# led-controller-hw.net
KiCad netlist of a schematic drawn in EAGLE
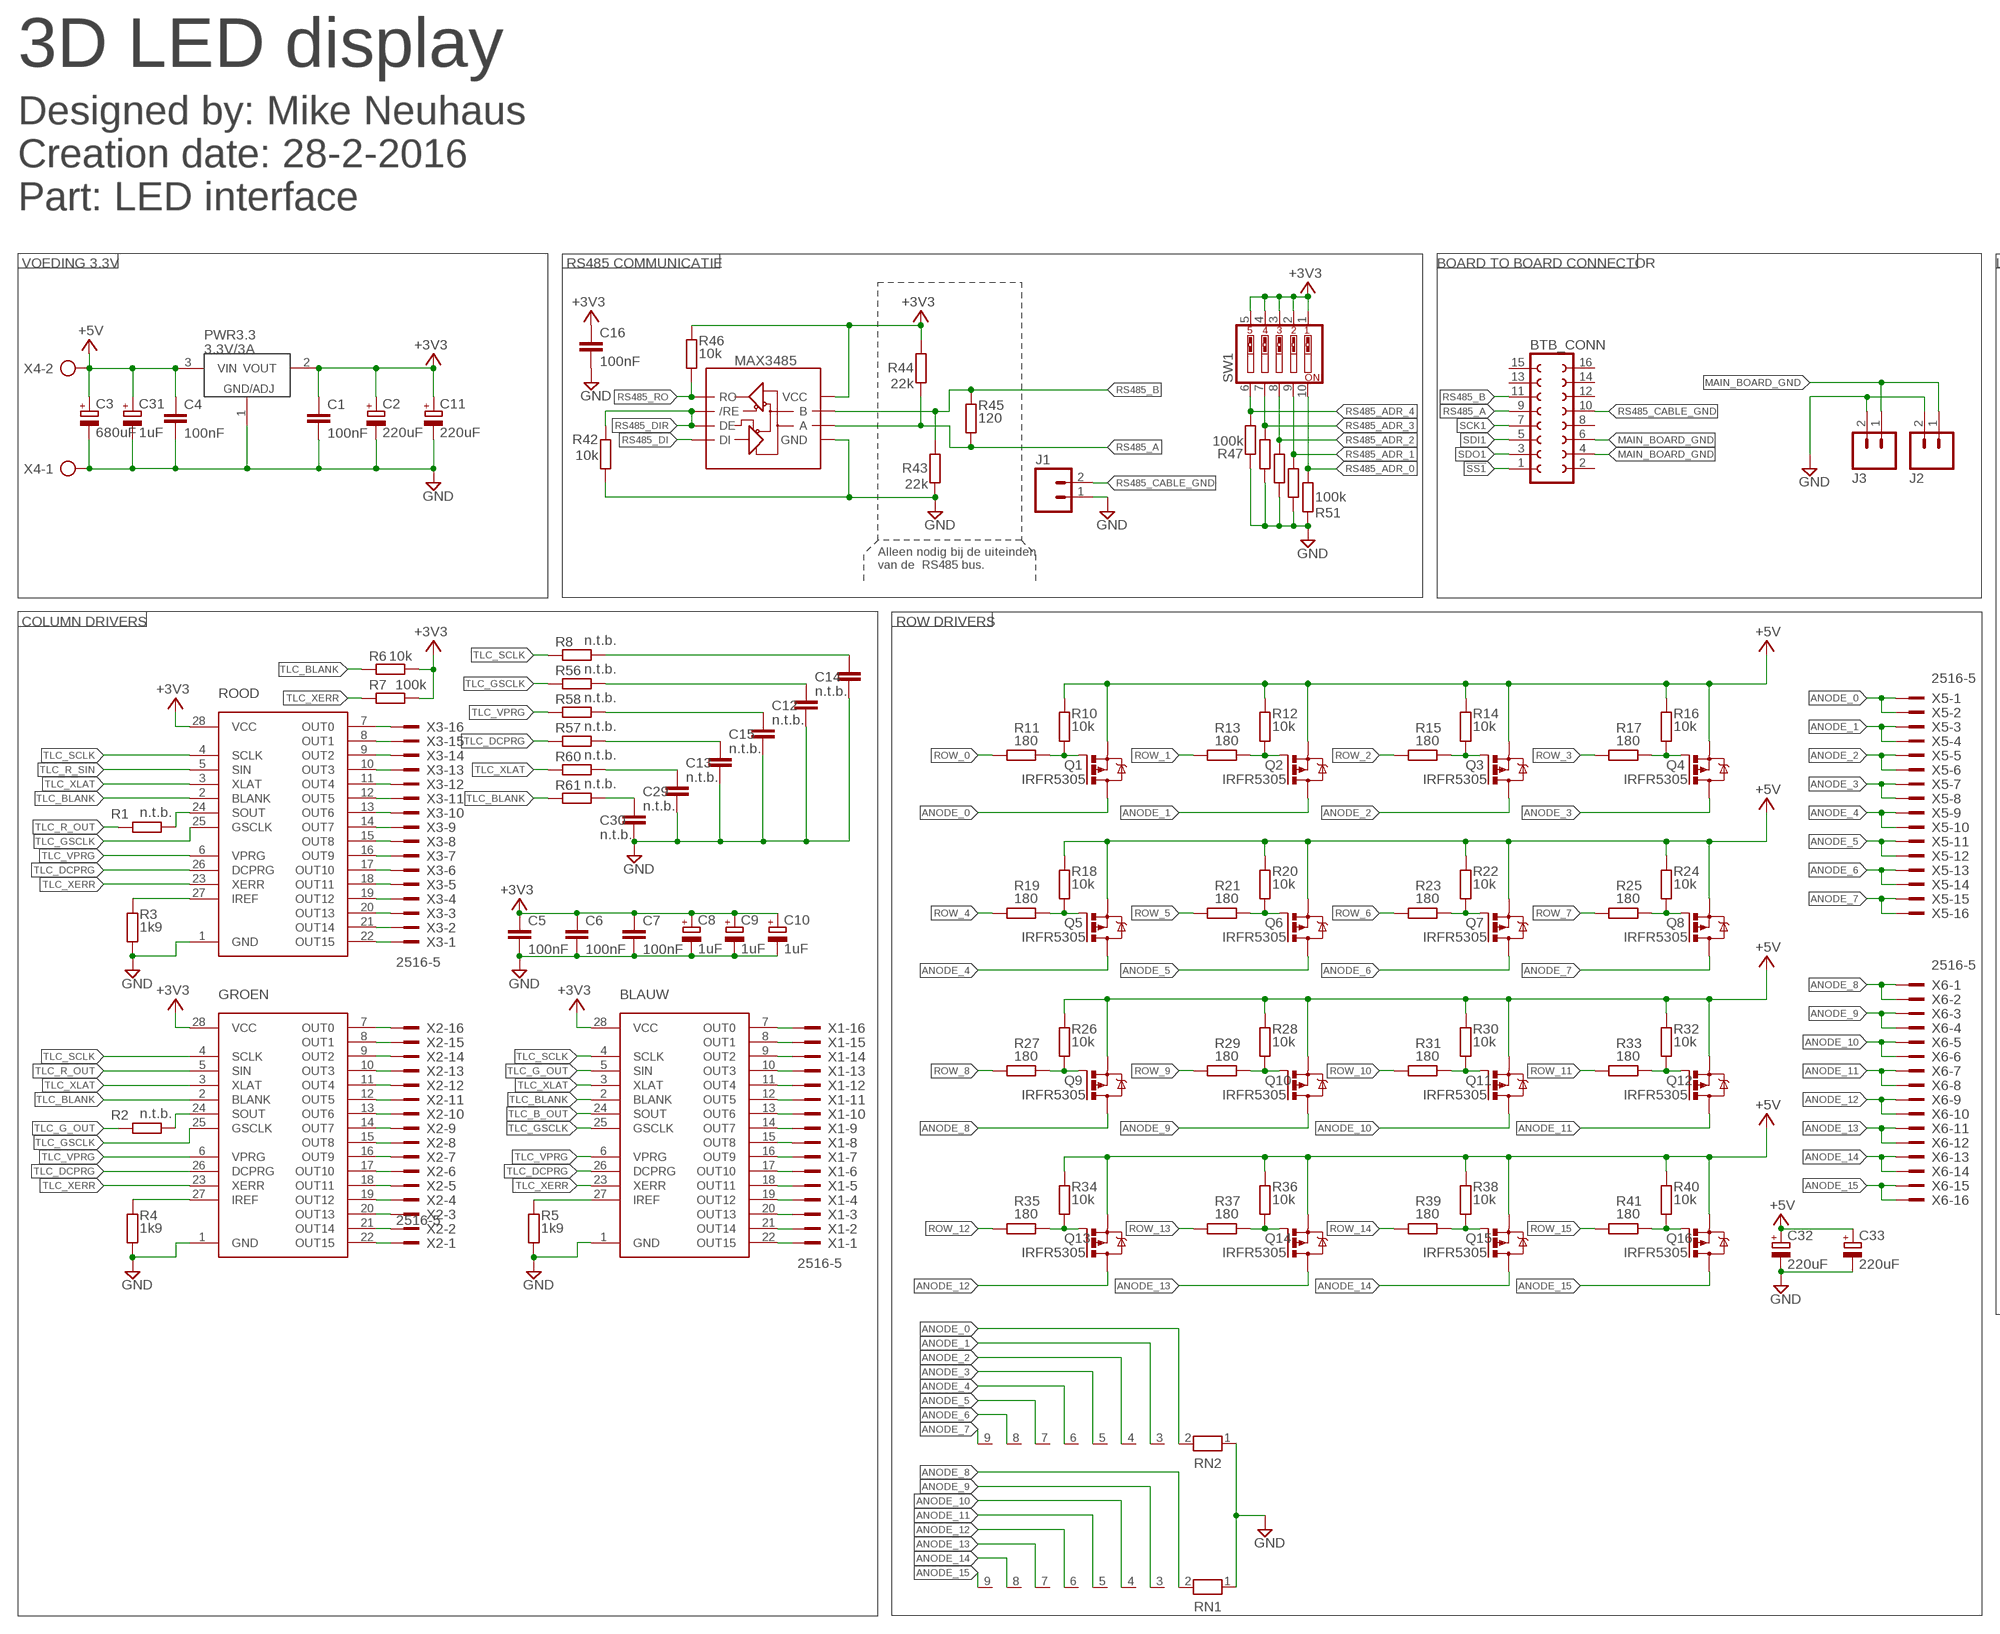
[diagram p0: schematic, sheet 1, part 1 of 2]
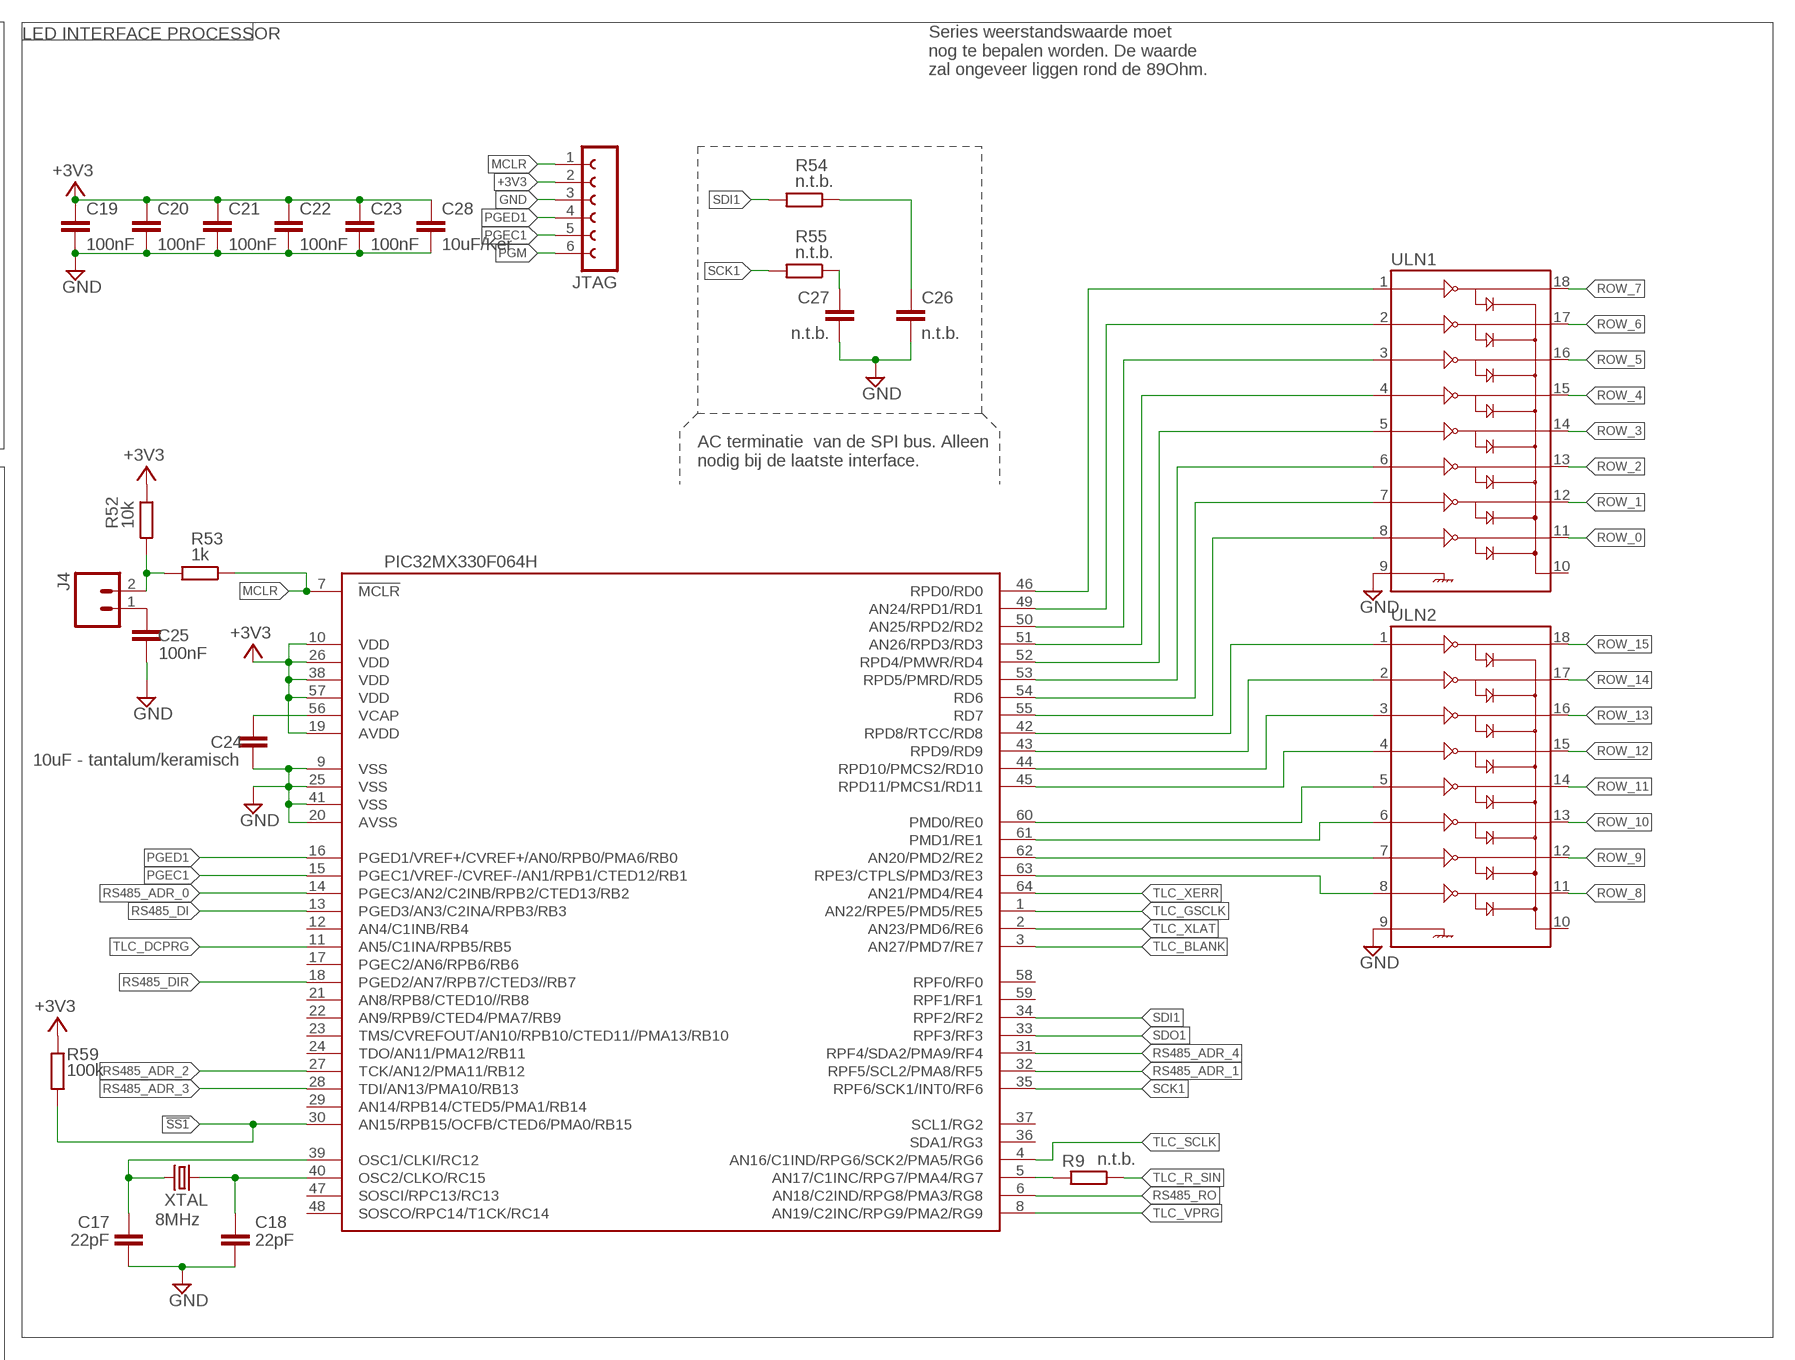
[diagram p1: schematic, sheet 1, part 2 of 2]

(export (version "E")
  (design (tool "Eeschema 10.0.6"))
  (components
    (comp (ref "BLAUW")
      (value "TLC5940PWPR")
      (footprint "eagle-import:TSSOP-28-PWP")
      (libsource (lib "eagle-import") (part "TLC5940PWPR"))
    )
    (comp (ref "BTB_CONN")
      (value "FE08-2W")
      (footprint "eagle-import:FE08-2W")
      (libsource (lib "eagle-import") (part "FE08-2W"))
    )
    (comp (ref "C1")
      (value "100nF")
      (footprint "eagle-import:C0805")
      (libsource (lib "eagle-import") (part "C-EUC0805"))
    )
    (comp (ref "C2")
      (value "220uF")
      (footprint "eagle-import:E2,5-6E")
      (libsource (lib "eagle-import") (part "CPOL-EUE2,5-6E"))
    )
    (comp (ref "C3")
      (value "680uF")
      (footprint "eagle-import:CPOL_EU10-27")
      (libsource (lib "eagle-import") (part "CPOL_EU10-27-5"))
    )
    (comp (ref "C4")
      (value "100nF")
      (footprint "eagle-import:C0805")
      (libsource (lib "eagle-import") (part "C-EUC0805"))
    )
    (comp (ref "C5")
      (value "100nF")
      (footprint "eagle-import:C0805")
      (libsource (lib "eagle-import") (part "C-EUC0805"))
    )
    (comp (ref "C6")
      (value "100nF")
      (footprint "eagle-import:C0805")
      (libsource (lib "eagle-import") (part "C-EUC0805"))
    )
    (comp (ref "C7")
      (value "100nF")
      (footprint "eagle-import:C0805")
      (libsource (lib "eagle-import") (part "C-EUC0805"))
    )
    (comp (ref "C8")
      (value "1uF")
      (footprint "eagle-import:E2,5-5")
      (libsource (lib "eagle-import") (part "CPOL-EUE2.5-5"))
    )
    (comp (ref "C9")
      (value "1uF")
      (footprint "eagle-import:E2,5-5")
      (libsource (lib "eagle-import") (part "CPOL-EUE2.5-5"))
    )
    (comp (ref "C10")
      (value "1uF")
      (footprint "eagle-import:E2,5-5")
      (libsource (lib "eagle-import") (part "CPOL-EUE2.5-5"))
    )
    (comp (ref "C11")
      (value "220uF")
      (footprint "eagle-import:E2,5-6E")
      (libsource (lib "eagle-import") (part "CPOL-EUE2,5-6E"))
    )
    (comp (ref "C12")
      (value "n.t.b.")
      (footprint "eagle-import:C0805")
      (libsource (lib "eagle-import") (part "C-EUC0805"))
    )
    (comp (ref "C13")
      (value "n.t.b.")
      (footprint "eagle-import:C0805")
      (libsource (lib "eagle-import") (part "C-EUC0805"))
    )
    (comp (ref "C14")
      (value "n.t.b.")
      (footprint "eagle-import:C0805")
      (libsource (lib "eagle-import") (part "C-EUC0805"))
    )
    (comp (ref "C15")
      (value "n.t.b.")
      (footprint "eagle-import:C0805")
      (libsource (lib "eagle-import") (part "C-EUC0805"))
    )
    (comp (ref "C16")
      (value "100nF")
      (footprint "eagle-import:C0805")
      (libsource (lib "eagle-import") (part "C-EUC0805"))
    )
    (comp (ref "C17")
      (value "22pF")
      (footprint "eagle-import:C0805")
      (libsource (lib "eagle-import") (part "C-EUC0805"))
    )
    (comp (ref "C18")
      (value "22pF")
      (footprint "eagle-import:C0805")
      (libsource (lib "eagle-import") (part "C-EUC0805"))
    )
    (comp (ref "C19")
      (value "100nF")
      (footprint "eagle-import:C0805")
      (libsource (lib "eagle-import") (part "C-EUC0805"))
    )
    (comp (ref "C20")
      (value "100nF")
      (footprint "eagle-import:C0805")
      (libsource (lib "eagle-import") (part "C-EUC0805"))
    )
    (comp (ref "C21")
      (value "100nF")
      (footprint "eagle-import:C0805")
      (libsource (lib "eagle-import") (part "C-EUC0805"))
    )
    (comp (ref "C22")
      (value "100nF")
      (footprint "eagle-import:C0805")
      (libsource (lib "eagle-import") (part "C-EUC0805"))
    )
    (comp (ref "C23")
      (value "100nF")
      (footprint "eagle-import:C0805")
      (libsource (lib "eagle-import") (part "C-EUC0805"))
    )
    (comp (ref "C24")
      (value "10uF - tantalum/keramisch")
      (footprint "eagle-import:C0805")
      (libsource (lib "eagle-import") (part "C-EUC0805"))
    )
    (comp (ref "C25")
      (value "100nF")
      (footprint "eagle-import:C0805")
      (libsource (lib "eagle-import") (part "C-EUC0805"))
    )
    (comp (ref "C26")
      (value "n.t.b.")
      (footprint "eagle-import:C0805")
      (libsource (lib "eagle-import") (part "C-EUC0805"))
    )
    (comp (ref "C27")
      (value "n.t.b.")
      (footprint "eagle-import:C0805")
      (libsource (lib "eagle-import") (part "C-EUC0805"))
    )
    (comp (ref "C28")
      (value "10uF/Ker")
      (footprint "eagle-import:C0805")
      (libsource (lib "eagle-import") (part "C-EUC0805"))
    )
    (comp (ref "C29")
      (value "n.t.b.")
      (footprint "eagle-import:C0805")
      (libsource (lib "eagle-import") (part "C-EUC0805"))
    )
    (comp (ref "C30")
      (value "n.t.b.")
      (footprint "eagle-import:C0805")
      (libsource (lib "eagle-import") (part "C-EUC0805"))
    )
    (comp (ref "C31")
      (value "1uF")
      (footprint "eagle-import:E2,5-5")
      (libsource (lib "eagle-import") (part "CPOL-EUE2.5-5"))
    )
    (comp (ref "C32")
      (value "220uF")
      (footprint "eagle-import:E2,5-6E")
      (libsource (lib "eagle-import") (part "CPOL-EUE2,5-6E"))
    )
    (comp (ref "C33")
      (value "220uF")
      (footprint "eagle-import:E2,5-6E")
      (libsource (lib "eagle-import") (part "CPOL-EUE2,5-6E"))
    )
    (comp (ref "GROEN")
      (value "TLC5940PWPR")
      (footprint "eagle-import:TSSOP-28-PWP")
      (libsource (lib "eagle-import") (part "TLC5940PWPR"))
    )
    (comp (ref "J1")
      (value "M02LOCK")
      (footprint "eagle-import:1X02_LOCK")
      (libsource (lib "eagle-import") (part "M02LOCK"))
    )
    (comp (ref "J2")
      (value "M02LOCK")
      (footprint "eagle-import:1X02_LOCK")
      (libsource (lib "eagle-import") (part "M02LOCK"))
    )
    (comp (ref "J3")
      (value "M02LOCK")
      (footprint "eagle-import:1X02_LOCK")
      (libsource (lib "eagle-import") (part "M02LOCK"))
    )
    (comp (ref "J4")
      (value "M02LOCK")
      (footprint "eagle-import:1X02_LOCK")
      (libsource (lib "eagle-import") (part "M02LOCK"))
    )
    (comp (ref "JTAG")
      (value "FE06-1")
      (footprint "eagle-import:FE06")
      (libsource (lib "eagle-import") (part "FE06-1"))
    )
    (comp (ref "MAX3485")
      (value "RS485SOIC")
      (footprint "eagle-import:SO08")
      (libsource (lib "eagle-import") (part "RS485SOIC"))
    )
    (comp (ref "PIC32MX330F064H")
      (value "PIC32MX330F064H")
      (footprint "eagle-import:TQFP-64-10")
      (libsource (lib "eagle-import") (part "PIC32MX330F064H"))
    )
    (comp (ref "PWR3.3")
      (value "3.3V/3A")
      (footprint "eagle-import:TO-220")
      (libsource (lib "eagle-import") (part "LM1085-3.3"))
    )
    (comp (ref "Q1")
      (value "IRFR5305")
      (footprint "eagle-import:D-PAK_TO252AA")
      (libsource (lib "eagle-import") (part "IRF?5305R"))
    )
    (comp (ref "Q2")
      (value "IRFR5305")
      (footprint "eagle-import:D-PAK_TO252AA")
      (libsource (lib "eagle-import") (part "IRF?5305R"))
    )
    (comp (ref "Q3")
      (value "IRFR5305")
      (footprint "eagle-import:D-PAK_TO252AA")
      (libsource (lib "eagle-import") (part "IRF?5305R"))
    )
    (comp (ref "Q4")
      (value "IRFR5305")
      (footprint "eagle-import:D-PAK_TO252AA")
      (libsource (lib "eagle-import") (part "IRF?5305R"))
    )
    (comp (ref "Q5")
      (value "IRFR5305")
      (footprint "eagle-import:D-PAK_TO252AA")
      (libsource (lib "eagle-import") (part "IRF?5305R"))
    )
    (comp (ref "Q6")
      (value "IRFR5305")
      (footprint "eagle-import:D-PAK_TO252AA")
      (libsource (lib "eagle-import") (part "IRF?5305R"))
    )
    (comp (ref "Q7")
      (value "IRFR5305")
      (footprint "eagle-import:D-PAK_TO252AA")
      (libsource (lib "eagle-import") (part "IRF?5305R"))
    )
    (comp (ref "Q8")
      (value "IRFR5305")
      (footprint "eagle-import:D-PAK_TO252AA")
      (libsource (lib "eagle-import") (part "IRF?5305R"))
    )
    (comp (ref "Q9")
      (value "IRFR5305")
      (footprint "eagle-import:D-PAK_TO252AA")
      (libsource (lib "eagle-import") (part "IRF?5305R"))
    )
    (comp (ref "Q10")
      (value "IRFR5305")
      (footprint "eagle-import:D-PAK_TO252AA")
      (libsource (lib "eagle-import") (part "IRF?5305R"))
    )
    (comp (ref "Q11")
      (value "IRFR5305")
      (footprint "eagle-import:D-PAK_TO252AA")
      (libsource (lib "eagle-import") (part "IRF?5305R"))
    )
    (comp (ref "Q12")
      (value "IRFR5305")
      (footprint "eagle-import:D-PAK_TO252AA")
      (libsource (lib "eagle-import") (part "IRF?5305R"))
    )
    (comp (ref "Q13")
      (value "IRFR5305")
      (footprint "eagle-import:D-PAK_TO252AA")
      (libsource (lib "eagle-import") (part "IRF?5305R"))
    )
    (comp (ref "Q14")
      (value "IRFR5305")
      (footprint "eagle-import:D-PAK_TO252AA")
      (libsource (lib "eagle-import") (part "IRF?5305R"))
    )
    (comp (ref "Q15")
      (value "IRFR5305")
      (footprint "eagle-import:D-PAK_TO252AA")
      (libsource (lib "eagle-import") (part "IRF?5305R"))
    )
    (comp (ref "Q16")
      (value "IRFR5305")
      (footprint "eagle-import:D-PAK_TO252AA")
      (libsource (lib "eagle-import") (part "IRF?5305R"))
    )
    (comp (ref "R1")
      (value "n.t.b.")
      (footprint "eagle-import:M0805")
      (libsource (lib "eagle-import") (part "R-EU_M0805"))
    )
    (comp (ref "R2")
      (value "n.t.b.")
      (footprint "eagle-import:M0805")
      (libsource (lib "eagle-import") (part "R-EU_M0805"))
    )
    (comp (ref "R3")
      (value "1k9")
      (footprint "eagle-import:M0805")
      (libsource (lib "eagle-import") (part "R-EU_M0805"))
    )
    (comp (ref "R4")
      (value "1k9")
      (footprint "eagle-import:M0805")
      (libsource (lib "eagle-import") (part "R-EU_M0805"))
    )
    (comp (ref "R5")
      (value "1k9")
      (footprint "eagle-import:M0805")
      (libsource (lib "eagle-import") (part "R-EU_M0805"))
    )
    (comp (ref "R6")
      (value "10k")
      (footprint "eagle-import:M0805")
      (libsource (lib "eagle-import") (part "R-EU_M0805"))
    )
    (comp (ref "R7")
      (value "100k")
      (footprint "eagle-import:M0805")
      (libsource (lib "eagle-import") (part "R-EU_M0805"))
    )
    (comp (ref "R8")
      (value "n.t.b.")
      (footprint "eagle-import:M0805")
      (libsource (lib "eagle-import") (part "R-EU_M0805"))
    )
    (comp (ref "R9")
      (value "n.t.b.")
      (footprint "eagle-import:M0805")
      (libsource (lib "eagle-import") (part "R-EU_M0805"))
    )
    (comp (ref "R10")
      (value "10k")
      (footprint "eagle-import:M0805")
      (libsource (lib "eagle-import") (part "R-EU_M0805"))
    )
    (comp (ref "R11")
      (value "180")
      (footprint "eagle-import:M0805")
      (libsource (lib "eagle-import") (part "R-EU_M0805"))
    )
    (comp (ref "R12")
      (value "10k")
      (footprint "eagle-import:M0805")
      (libsource (lib "eagle-import") (part "R-EU_M0805"))
    )
    (comp (ref "R13")
      (value "180")
      (footprint "eagle-import:M0805")
      (libsource (lib "eagle-import") (part "R-EU_M0805"))
    )
    (comp (ref "R14")
      (value "10k")
      (footprint "eagle-import:M0805")
      (libsource (lib "eagle-import") (part "R-EU_M0805"))
    )
    (comp (ref "R15")
      (value "180")
      (footprint "eagle-import:M0805")
      (libsource (lib "eagle-import") (part "R-EU_M0805"))
    )
    (comp (ref "R16")
      (value "10k")
      (footprint "eagle-import:M0805")
      (libsource (lib "eagle-import") (part "R-EU_M0805"))
    )
    (comp (ref "R17")
      (value "180")
      (footprint "eagle-import:M0805")
      (libsource (lib "eagle-import") (part "R-EU_M0805"))
    )
    (comp (ref "R18")
      (value "10k")
      (footprint "eagle-import:M0805")
      (libsource (lib "eagle-import") (part "R-EU_M0805"))
    )
    (comp (ref "R19")
      (value "180")
      (footprint "eagle-import:M0805")
      (libsource (lib "eagle-import") (part "R-EU_M0805"))
    )
    (comp (ref "R20")
      (value "10k")
      (footprint "eagle-import:M0805")
      (libsource (lib "eagle-import") (part "R-EU_M0805"))
    )
    (comp (ref "R21")
      (value "180")
      (footprint "eagle-import:M0805")
      (libsource (lib "eagle-import") (part "R-EU_M0805"))
    )
    (comp (ref "R22")
      (value "10k")
      (footprint "eagle-import:M0805")
      (libsource (lib "eagle-import") (part "R-EU_M0805"))
    )
    (comp (ref "R23")
      (value "180")
      (footprint "eagle-import:M0805")
      (libsource (lib "eagle-import") (part "R-EU_M0805"))
    )
    (comp (ref "R24")
      (value "10k")
      (footprint "eagle-import:M0805")
      (libsource (lib "eagle-import") (part "R-EU_M0805"))
    )
    (comp (ref "R25")
      (value "180")
      (footprint "eagle-import:M0805")
      (libsource (lib "eagle-import") (part "R-EU_M0805"))
    )
    (comp (ref "R26")
      (value "10k")
      (footprint "eagle-import:M0805")
      (libsource (lib "eagle-import") (part "R-EU_M0805"))
    )
    (comp (ref "R27")
      (value "180")
      (footprint "eagle-import:M0805")
      (libsource (lib "eagle-import") (part "R-EU_M0805"))
    )
    (comp (ref "R28")
      (value "10k")
      (footprint "eagle-import:M0805")
      (libsource (lib "eagle-import") (part "R-EU_M0805"))
    )
    (comp (ref "R29")
      (value "180")
      (footprint "eagle-import:M0805")
      (libsource (lib "eagle-import") (part "R-EU_M0805"))
    )
    (comp (ref "R30")
      (value "10k")
      (footprint "eagle-import:M0805")
      (libsource (lib "eagle-import") (part "R-EU_M0805"))
    )
    (comp (ref "R31")
      (value "180")
      (footprint "eagle-import:M0805")
      (libsource (lib "eagle-import") (part "R-EU_M0805"))
    )
    (comp (ref "R32")
      (value "10k")
      (footprint "eagle-import:M0805")
      (libsource (lib "eagle-import") (part "R-EU_M0805"))
    )
    (comp (ref "R33")
      (value "180")
      (footprint "eagle-import:M0805")
      (libsource (lib "eagle-import") (part "R-EU_M0805"))
    )
    (comp (ref "R34")
      (value "10k")
      (footprint "eagle-import:M0805")
      (libsource (lib "eagle-import") (part "R-EU_M0805"))
    )
    (comp (ref "R35")
      (value "180")
      (footprint "eagle-import:M0805")
      (libsource (lib "eagle-import") (part "R-EU_M0805"))
    )
    (comp (ref "R36")
      (value "10k")
      (footprint "eagle-import:M0805")
      (libsource (lib "eagle-import") (part "R-EU_M0805"))
    )
    (comp (ref "R37")
      (value "180")
      (footprint "eagle-import:M0805")
      (libsource (lib "eagle-import") (part "R-EU_M0805"))
    )
    (comp (ref "R38")
      (value "10k")
      (footprint "eagle-import:M0805")
      (libsource (lib "eagle-import") (part "R-EU_M0805"))
    )
    (comp (ref "R39")
      (value "180")
      (footprint "eagle-import:M0805")
      (libsource (lib "eagle-import") (part "R-EU_M0805"))
    )
    (comp (ref "R40")
      (value "10k")
      (footprint "eagle-import:M0805")
      (libsource (lib "eagle-import") (part "R-EU_M0805"))
    )
    (comp (ref "R41")
      (value "180")
      (footprint "eagle-import:M0805")
      (libsource (lib "eagle-import") (part "R-EU_M0805"))
    )
    (comp (ref "R42")
      (value "10k")
      (footprint "eagle-import:M0805")
      (libsource (lib "eagle-import") (part "R-EU_M0805"))
    )
    (comp (ref "R43")
      (value "22k")
      (footprint "eagle-import:M0805")
      (libsource (lib "eagle-import") (part "R-EU_M0805"))
    )
    (comp (ref "R44")
      (value "22k")
      (footprint "eagle-import:M0805")
      (libsource (lib "eagle-import") (part "R-EU_M0805"))
    )
    (comp (ref "R45")
      (value "120")
      (footprint "eagle-import:M0805")
      (libsource (lib "eagle-import") (part "R-EU_M0805"))
    )
    (comp (ref "R46")
      (value "10k")
      (footprint "eagle-import:M0805")
      (libsource (lib "eagle-import") (part "R-EU_M0805"))
    )
    (comp (ref "R47")
      (value "100k")
      (footprint "eagle-import:M0805")
      (libsource (lib "eagle-import") (part "R-EU_M0805"))
    )
    (comp (ref "R48")
      (value "100k")
      (footprint "eagle-import:M0805")
      (libsource (lib "eagle-import") (part "R-EU_M0805"))
    )
    (comp (ref "R49")
      (value "100k")
      (footprint "eagle-import:M0805")
      (libsource (lib "eagle-import") (part "R-EU_M0805"))
    )
    (comp (ref "R50")
      (value "100k")
      (footprint "eagle-import:M0805")
      (libsource (lib "eagle-import") (part "R-EU_M0805"))
    )
    (comp (ref "R51")
      (value "100k")
      (footprint "eagle-import:M0805")
      (libsource (lib "eagle-import") (part "R-EU_M0805"))
    )
    (comp (ref "R52")
      (value "10k")
      (footprint "eagle-import:M0805")
      (libsource (lib "eagle-import") (part "R-EU_M0805"))
    )
    (comp (ref "R53")
      (value "1k")
      (footprint "eagle-import:M0805")
      (libsource (lib "eagle-import") (part "R-EU_M0805"))
    )
    (comp (ref "R54")
      (value "n.t.b.")
      (footprint "eagle-import:M0805")
      (libsource (lib "eagle-import") (part "R-EU_M0805"))
    )
    (comp (ref "R55")
      (value "n.t.b.")
      (footprint "eagle-import:M0805")
      (libsource (lib "eagle-import") (part "R-EU_M0805"))
    )
    (comp (ref "R56")
      (value "n.t.b.")
      (footprint "eagle-import:M0805")
      (libsource (lib "eagle-import") (part "R-EU_M0805"))
    )
    (comp (ref "R57")
      (value "n.t.b.")
      (footprint "eagle-import:M0805")
      (libsource (lib "eagle-import") (part "R-EU_M0805"))
    )
    (comp (ref "R58")
      (value "n.t.b.")
      (footprint "eagle-import:M0805")
      (libsource (lib "eagle-import") (part "R-EU_M0805"))
    )
    (comp (ref "R59")
      (value "100k")
      (footprint "eagle-import:M0805")
      (libsource (lib "eagle-import") (part "R-EU_M0805"))
    )
    (comp (ref "R60")
      (value "n.t.b.")
      (footprint "eagle-import:M0805")
      (libsource (lib "eagle-import") (part "R-EU_M0805"))
    )
    (comp (ref "R61")
      (value "n.t.b.")
      (footprint "eagle-import:M0805")
      (libsource (lib "eagle-import") (part "R-EU_M0805"))
    )
    (comp (ref "RN1")
      (value "RN08")
      (footprint "eagle-import:RN-9")
      (libsource (lib "eagle-import") (part "RN08"))
    )
    (comp (ref "RN2")
      (value "RN08")
      (footprint "eagle-import:RN-9")
      (libsource (lib "eagle-import") (part "RN08"))
    )
    (comp (ref "ROOD")
      (value "TLC5940PWPR")
      (footprint "eagle-import:TSSOP-28-PWP")
      (libsource (lib "eagle-import") (part "TLC5940PWPR"))
    )
    (comp (ref "SW1")
      (value "SW_DIP-5")
      (footprint "eagle-import:EDG-05")
      (libsource (lib "eagle-import") (part "SW_DIP-5"))
    )
    (comp (ref "ULN1")
      (value "ULN2803SOICW")
      (footprint "eagle-import:SO18L")
      (libsource (lib "eagle-import") (part "ULN2803SOICW"))
    )
    (comp (ref "ULN2")
      (value "ULN2803SOICW")
      (footprint "eagle-import:SO18L")
      (libsource (lib "eagle-import") (part "ULN2803SOICW"))
    )
    (comp (ref "X1")
      (value "2516-5")
      (footprint "eagle-import:PAK100_2500-5-16")
      (fields (field (name "MPN") "D2516-5002-AR"))
      (libsource (lib "eagle-import") (part "2516-5"))
    )
    (comp (ref "X2")
      (value "2516-5")
      (footprint "eagle-import:PAK100_2500-5-16")
      (fields (field (name "MPN") "D2516-5002-AR"))
      (libsource (lib "eagle-import") (part "2516-5"))
    )
    (comp (ref "X3")
      (value "2516-5")
      (footprint "eagle-import:PAK100_2500-5-16")
      (fields (field (name "MPN") "D2516-5002-AR"))
      (libsource (lib "eagle-import") (part "2516-5"))
    )
    (comp (ref "X4")
      (value "AK500/2-H")
      (footprint "eagle-import:AK500_2-H")
      (libsource (lib "eagle-import") (part "AK500/2-H"))
    )
    (comp (ref "X5")
      (value "2516-5")
      (footprint "eagle-import:PAK100_2500-5-16")
      (fields (field (name "MPN") "D2516-5002-AR"))
      (libsource (lib "eagle-import") (part "2516-5"))
    )
    (comp (ref "X6")
      (value "2516-5")
      (footprint "eagle-import:PAK100_2500-5-16")
      (fields (field (name "MPN") "D2516-5002-AR"))
      (libsource (lib "eagle-import") (part "2516-5"))
    )
    (comp (ref "XTAL")
      (value "8MHz")
      (footprint "eagle-import:CSM-7X-DU")
      (libsource (lib "eagle-import") (part "CSM-7X-DU"))
    )
  )
  (nets
    (net (code "1") (name "+3V3") (class "Default")
      (node (ref "BLAUW") (pin "28") (pinfunction "VCC_28") (pintype "power_in"))
      (node (ref "C1") (pin "1") (pinfunction "1_1") (pintype "passive"))
      (node (ref "C10") (pin "+") (pinfunction "+_+") (pintype "passive"))
      (node (ref "C11") (pin "+") (pinfunction "+_+") (pintype "passive"))
      (node (ref "C16") (pin "1") (pinfunction "1_1") (pintype "passive"))
      (node (ref "C19") (pin "1") (pinfunction "1_1") (pintype "passive"))
      (node (ref "C2") (pin "+") (pinfunction "+_+") (pintype "passive"))
      (node (ref "C20") (pin "1") (pinfunction "1_1") (pintype "passive"))
      (node (ref "C21") (pin "1") (pinfunction "1_1") (pintype "passive"))
      (node (ref "C22") (pin "1") (pinfunction "1_1") (pintype "passive"))
      (node (ref "C23") (pin "1") (pinfunction "1_1") (pintype "passive"))
      (node (ref "C28") (pin "1") (pinfunction "1_1") (pintype "passive"))
      (node (ref "C5") (pin "1") (pinfunction "1_1") (pintype "passive"))
      (node (ref "C6") (pin "1") (pinfunction "1_1") (pintype "passive"))
      (node (ref "C7") (pin "1") (pinfunction "1_1") (pintype "passive"))
      (node (ref "C8") (pin "+") (pinfunction "+_+") (pintype "passive"))
      (node (ref "C9") (pin "+") (pinfunction "+_+") (pintype "passive"))
      (node (ref "GROEN") (pin "28") (pinfunction "VCC_28") (pintype "power_in"))
      (node (ref "JTAG") (pin "2") (pinfunction "2_2") (pintype "passive"))
      (node (ref "MAX3485") (pin "8") (pinfunction "VCC_8") (pintype "bidirectional"))
      (node (ref "PIC32MX330F064H") (pin "10") (pinfunction "VDD_10") (pintype "power_in"))
      (node (ref "PIC32MX330F064H") (pin "19") (pinfunction "AVDD_19") (pintype "power_in"))
      (node (ref "PIC32MX330F064H") (pin "26") (pinfunction "VDD_26") (pintype "power_in"))
      (node (ref "PIC32MX330F064H") (pin "38") (pinfunction "VDD_38") (pintype "power_in"))
      (node (ref "PIC32MX330F064H") (pin "57") (pinfunction "VDD_57") (pintype "power_in"))
      (node (ref "PWR3.3") (pin "2") (pinfunction "VOUT_2") (pintype "power_in"))
      (node (ref "R44") (pin "1") (pinfunction "1_1") (pintype "passive"))
      (node (ref "R46") (pin "2") (pinfunction "2_2") (pintype "passive"))
      (node (ref "R52") (pin "1") (pinfunction "1_1") (pintype "passive"))
      (node (ref "R59") (pin "1") (pinfunction "1_1") (pintype "passive"))
      (node (ref "R6") (pin "2") (pinfunction "2_2") (pintype "passive"))
      (node (ref "R7") (pin "2") (pinfunction "2_2") (pintype "passive"))
      (node (ref "ROOD") (pin "28") (pinfunction "VCC_28") (pintype "power_in"))
      (node (ref "SW1") (pin "1") (pinfunction "1_1") (pintype "passive"))
      (node (ref "SW1") (pin "2") (pinfunction "2_2") (pintype "passive"))
      (node (ref "SW1") (pin "3") (pinfunction "3_3") (pintype "passive"))
      (node (ref "SW1") (pin "4") (pinfunction "4_4") (pintype "passive"))
      (node (ref "SW1") (pin "5") (pinfunction "5_5") (pintype "passive"))
    )
    (net (code "2") (name "+5V") (class "Default")
      (node (ref "C3") (pin "1") (pinfunction "+_1") (pintype "passive"))
      (node (ref "C31") (pin "+") (pinfunction "+_+") (pintype "passive"))
      (node (ref "C32") (pin "+") (pinfunction "+_+") (pintype "passive"))
      (node (ref "C33") (pin "+") (pinfunction "+_+") (pintype "passive"))
      (node (ref "C4") (pin "1") (pinfunction "1_1") (pintype "passive"))
      (node (ref "PWR3.3") (pin "3") (pinfunction "VIN_3") (pintype "power_in"))
      (node (ref "Q1") (pin "3") (pinfunction "S_3") (pintype "passive"))
      (node (ref "Q10") (pin "3") (pinfunction "S_3") (pintype "passive"))
      (node (ref "Q11") (pin "3") (pinfunction "S_3") (pintype "passive"))
      (node (ref "Q12") (pin "3") (pinfunction "S_3") (pintype "passive"))
      (node (ref "Q13") (pin "3") (pinfunction "S_3") (pintype "passive"))
      (node (ref "Q14") (pin "3") (pinfunction "S_3") (pintype "passive"))
      (node (ref "Q15") (pin "3") (pinfunction "S_3") (pintype "passive"))
      (node (ref "Q16") (pin "3") (pinfunction "S_3") (pintype "passive"))
      (node (ref "Q2") (pin "3") (pinfunction "S_3") (pintype "passive"))
      (node (ref "Q3") (pin "3") (pinfunction "S_3") (pintype "passive"))
      (node (ref "Q4") (pin "3") (pinfunction "S_3") (pintype "passive"))
      (node (ref "Q5") (pin "3") (pinfunction "S_3") (pintype "passive"))
      (node (ref "Q6") (pin "3") (pinfunction "S_3") (pintype "passive"))
      (node (ref "Q7") (pin "3") (pinfunction "S_3") (pintype "passive"))
      (node (ref "Q8") (pin "3") (pinfunction "S_3") (pintype "passive"))
      (node (ref "Q9") (pin "3") (pinfunction "S_3") (pintype "passive"))
      (node (ref "R10") (pin "2") (pinfunction "2_2") (pintype "passive"))
      (node (ref "R12") (pin "2") (pinfunction "2_2") (pintype "passive"))
      (node (ref "R14") (pin "2") (pinfunction "2_2") (pintype "passive"))
      (node (ref "R16") (pin "2") (pinfunction "2_2") (pintype "passive"))
      (node (ref "R18") (pin "2") (pinfunction "2_2") (pintype "passive"))
      (node (ref "R20") (pin "2") (pinfunction "2_2") (pintype "passive"))
      (node (ref "R22") (pin "2") (pinfunction "2_2") (pintype "passive"))
      (node (ref "R24") (pin "2") (pinfunction "2_2") (pintype "passive"))
      (node (ref "R26") (pin "2") (pinfunction "2_2") (pintype "passive"))
      (node (ref "R28") (pin "2") (pinfunction "2_2") (pintype "passive"))
      (node (ref "R30") (pin "2") (pinfunction "2_2") (pintype "passive"))
      (node (ref "R32") (pin "2") (pinfunction "2_2") (pintype "passive"))
      (node (ref "R34") (pin "2") (pinfunction "2_2") (pintype "passive"))
      (node (ref "R36") (pin "2") (pinfunction "2_2") (pintype "passive"))
      (node (ref "R38") (pin "2") (pinfunction "2_2") (pintype "passive"))
      (node (ref "R40") (pin "2") (pinfunction "2_2") (pintype "passive"))
      (node (ref "X4") (pin "2") (pinfunction "KL_2") (pintype "passive"))
    )
    (net (code "3") (name "/~{SS1}") (class "Default")
      (node (ref "BTB_CONN") (pin "1") (pinfunction "1_1") (pintype "passive"))
      (node (ref "PIC32MX330F064H") (pin "30") (pinfunction "AN15/RPB15/OCFB/CTED6/PMA0/RB15_30") (pintype "bidirectional"))
      (node (ref "R59") (pin "2") (pinfunction "2_2") (pintype "passive"))
    )
    (net (code "4") (name "ANODE_0") (class "Default")
      (node (ref "Q1") (pin "4") (pinfunction "D_4") (pintype "passive"))
      (node (ref "RN2") (pin "2") (pinfunction "2_2") (pintype "passive"))
      (node (ref "X5") (pin "1") (pinfunction "KL_1") (pintype "passive"))
      (node (ref "X5") (pin "2") (pinfunction "KL_2") (pintype "passive"))
    )
    (net (code "5") (name "ANODE_1") (class "Default")
      (node (ref "Q2") (pin "4") (pinfunction "D_4") (pintype "passive"))
      (node (ref "RN2") (pin "3") (pinfunction "3_3") (pintype "passive"))
      (node (ref "X5") (pin "3") (pinfunction "KL_3") (pintype "passive"))
      (node (ref "X5") (pin "4") (pinfunction "KL_4") (pintype "passive"))
    )
    (net (code "6") (name "ANODE_2") (class "Default")
      (node (ref "Q3") (pin "4") (pinfunction "D_4") (pintype "passive"))
      (node (ref "RN2") (pin "4") (pinfunction "4_4") (pintype "passive"))
      (node (ref "X5") (pin "5") (pinfunction "KL_5") (pintype "passive"))
      (node (ref "X5") (pin "6") (pinfunction "KL_6") (pintype "passive"))
    )
    (net (code "7") (name "ANODE_3") (class "Default")
      (node (ref "Q4") (pin "4") (pinfunction "D_4") (pintype "passive"))
      (node (ref "RN2") (pin "5") (pinfunction "5_5") (pintype "passive"))
      (node (ref "X5") (pin "7") (pinfunction "KL_7") (pintype "passive"))
      (node (ref "X5") (pin "8") (pinfunction "KL_8") (pintype "passive"))
    )
    (net (code "8") (name "ANODE_4") (class "Default")
      (node (ref "Q5") (pin "4") (pinfunction "D_4") (pintype "passive"))
      (node (ref "RN2") (pin "6") (pinfunction "6_6") (pintype "passive"))
      (node (ref "X5") (pin "10") (pinfunction "KL_10") (pintype "passive"))
      (node (ref "X5") (pin "9") (pinfunction "KL_9") (pintype "passive"))
    )
    (net (code "9") (name "ANODE_5") (class "Default")
      (node (ref "Q6") (pin "4") (pinfunction "D_4") (pintype "passive"))
      (node (ref "RN2") (pin "7") (pinfunction "7_7") (pintype "passive"))
      (node (ref "X5") (pin "11") (pinfunction "KL_11") (pintype "passive"))
      (node (ref "X5") (pin "12") (pinfunction "KL_12") (pintype "passive"))
    )
    (net (code "10") (name "ANODE_6") (class "Default")
      (node (ref "Q7") (pin "4") (pinfunction "D_4") (pintype "passive"))
      (node (ref "RN2") (pin "8") (pinfunction "8_8") (pintype "passive"))
      (node (ref "X5") (pin "13") (pinfunction "KL_13") (pintype "passive"))
      (node (ref "X5") (pin "14") (pinfunction "KL_14") (pintype "passive"))
    )
    (net (code "11") (name "ANODE_7") (class "Default")
      (node (ref "Q8") (pin "4") (pinfunction "D_4") (pintype "passive"))
      (node (ref "RN2") (pin "9") (pinfunction "9_9") (pintype "passive"))
      (node (ref "X5") (pin "15") (pinfunction "KL_15") (pintype "passive"))
      (node (ref "X5") (pin "16") (pinfunction "KL_16") (pintype "passive"))
    )
    (net (code "12") (name "ANODE_8") (class "Default")
      (node (ref "Q9") (pin "4") (pinfunction "D_4") (pintype "passive"))
      (node (ref "RN1") (pin "2") (pinfunction "2_2") (pintype "passive"))
      (node (ref "X6") (pin "1") (pinfunction "KL_1") (pintype "passive"))
      (node (ref "X6") (pin "2") (pinfunction "KL_2") (pintype "passive"))
    )
    (net (code "13") (name "ANODE_9") (class "Default")
      (node (ref "Q10") (pin "4") (pinfunction "D_4") (pintype "passive"))
      (node (ref "RN1") (pin "3") (pinfunction "3_3") (pintype "passive"))
      (node (ref "X6") (pin "3") (pinfunction "KL_3") (pintype "passive"))
      (node (ref "X6") (pin "4") (pinfunction "KL_4") (pintype "passive"))
    )
    (net (code "14") (name "ANODE_10") (class "Default")
      (node (ref "Q11") (pin "4") (pinfunction "D_4") (pintype "passive"))
      (node (ref "RN1") (pin "4") (pinfunction "4_4") (pintype "passive"))
      (node (ref "X6") (pin "5") (pinfunction "KL_5") (pintype "passive"))
      (node (ref "X6") (pin "6") (pinfunction "KL_6") (pintype "passive"))
    )
    (net (code "15") (name "ANODE_11") (class "Default")
      (node (ref "Q12") (pin "4") (pinfunction "D_4") (pintype "passive"))
      (node (ref "RN1") (pin "5") (pinfunction "5_5") (pintype "passive"))
      (node (ref "X6") (pin "7") (pinfunction "KL_7") (pintype "passive"))
      (node (ref "X6") (pin "8") (pinfunction "KL_8") (pintype "passive"))
    )
    (net (code "16") (name "ANODE_12") (class "Default")
      (node (ref "Q13") (pin "4") (pinfunction "D_4") (pintype "passive"))
      (node (ref "RN1") (pin "6") (pinfunction "6_6") (pintype "passive"))
      (node (ref "X6") (pin "10") (pinfunction "KL_10") (pintype "passive"))
      (node (ref "X6") (pin "9") (pinfunction "KL_9") (pintype "passive"))
    )
    (net (code "17") (name "ANODE_13") (class "Default")
      (node (ref "Q14") (pin "4") (pinfunction "D_4") (pintype "passive"))
      (node (ref "RN1") (pin "7") (pinfunction "7_7") (pintype "passive"))
      (node (ref "X6") (pin "11") (pinfunction "KL_11") (pintype "passive"))
      (node (ref "X6") (pin "12") (pinfunction "KL_12") (pintype "passive"))
    )
    (net (code "18") (name "ANODE_14") (class "Default")
      (node (ref "Q15") (pin "4") (pinfunction "D_4") (pintype "passive"))
      (node (ref "RN1") (pin "8") (pinfunction "8_8") (pintype "passive"))
      (node (ref "X6") (pin "13") (pinfunction "KL_13") (pintype "passive"))
      (node (ref "X6") (pin "14") (pinfunction "KL_14") (pintype "passive"))
    )
    (net (code "19") (name "ANODE_15") (class "Default")
      (node (ref "Q16") (pin "4") (pinfunction "D_4") (pintype "passive"))
      (node (ref "RN1") (pin "9") (pinfunction "9_9") (pintype "passive"))
      (node (ref "X6") (pin "15") (pinfunction "KL_15") (pintype "passive"))
      (node (ref "X6") (pin "16") (pinfunction "KL_16") (pintype "passive"))
    )
    (net (code "20") (name "GND") (class "Default")
      (node (ref "BLAUW") (pin "1") (pinfunction "GND_1") (pintype "power_in"))
      (node (ref "C1") (pin "2") (pinfunction "2_2") (pintype "passive"))
      (node (ref "C10") (pin "-") (pinfunction "-_-") (pintype "passive"))
      (node (ref "C11") (pin "-") (pinfunction "-_-") (pintype "passive"))
      (node (ref "C12") (pin "2") (pinfunction "2_2") (pintype "passive"))
      (node (ref "C13") (pin "2") (pinfunction "2_2") (pintype "passive"))
      (node (ref "C14") (pin "2") (pinfunction "2_2") (pintype "passive"))
      (node (ref "C15") (pin "2") (pinfunction "2_2") (pintype "passive"))
      (node (ref "C16") (pin "2") (pinfunction "2_2") (pintype "passive"))
      (node (ref "C17") (pin "1") (pinfunction "1_1") (pintype "passive"))
      (node (ref "C18") (pin "1") (pinfunction "1_1") (pintype "passive"))
      (node (ref "C19") (pin "2") (pinfunction "2_2") (pintype "passive"))
      (node (ref "C2") (pin "-") (pinfunction "-_-") (pintype "passive"))
      (node (ref "C20") (pin "2") (pinfunction "2_2") (pintype "passive"))
      (node (ref "C21") (pin "2") (pinfunction "2_2") (pintype "passive"))
      (node (ref "C22") (pin "2") (pinfunction "2_2") (pintype "passive"))
      (node (ref "C23") (pin "2") (pinfunction "2_2") (pintype "passive"))
      (node (ref "C24") (pin "2") (pinfunction "2_2") (pintype "passive"))
      (node (ref "C25") (pin "2") (pinfunction "2_2") (pintype "passive"))
      (node (ref "C26") (pin "2") (pinfunction "2_2") (pintype "passive"))
      (node (ref "C27") (pin "2") (pinfunction "2_2") (pintype "passive"))
      (node (ref "C28") (pin "2") (pinfunction "2_2") (pintype "passive"))
      (node (ref "C29") (pin "2") (pinfunction "2_2") (pintype "passive"))
      (node (ref "C3") (pin "2") (pinfunction "-_2") (pintype "passive"))
      (node (ref "C30") (pin "2") (pinfunction "2_2") (pintype "passive"))
      (node (ref "C31") (pin "-") (pinfunction "-_-") (pintype "passive"))
      (node (ref "C32") (pin "-") (pinfunction "-_-") (pintype "passive"))
      (node (ref "C33") (pin "-") (pinfunction "-_-") (pintype "passive"))
      (node (ref "C4") (pin "2") (pinfunction "2_2") (pintype "passive"))
      (node (ref "C5") (pin "2") (pinfunction "2_2") (pintype "passive"))
      (node (ref "C6") (pin "2") (pinfunction "2_2") (pintype "passive"))
      (node (ref "C7") (pin "2") (pinfunction "2_2") (pintype "passive"))
      (node (ref "C8") (pin "-") (pinfunction "-_-") (pintype "passive"))
      (node (ref "C9") (pin "-") (pinfunction "-_-") (pintype "passive"))
      (node (ref "GROEN") (pin "1") (pinfunction "GND_1") (pintype "power_in"))
      (node (ref "J1") (pin "1") (pinfunction "1_1") (pintype "passive"))
      (node (ref "J2") (pin "2") (pinfunction "2_2") (pintype "passive"))
      (node (ref "J3") (pin "2") (pinfunction "2_2") (pintype "passive"))
      (node (ref "JTAG") (pin "3") (pinfunction "3_3") (pintype "passive"))
      (node (ref "MAX3485") (pin "5") (pinfunction "GND_5") (pintype "bidirectional"))
      (node (ref "PIC32MX330F064H") (pin "20") (pinfunction "AVSS_20") (pintype "power_in"))
      (node (ref "PIC32MX330F064H") (pin "25") (pinfunction "VSS_25") (pintype "power_in"))
      (node (ref "PIC32MX330F064H") (pin "41") (pinfunction "VSS_41") (pintype "power_in"))
      (node (ref "PIC32MX330F064H") (pin "9") (pinfunction "VSS_9") (pintype "power_in"))
      (node (ref "PWR3.3") (pin "1") (pinfunction "GND/ADJ_1") (pintype "power_in"))
      (node (ref "R3") (pin "1") (pinfunction "1_1") (pintype "passive"))
      (node (ref "R4") (pin "1") (pinfunction "1_1") (pintype "passive"))
      (node (ref "R42") (pin "2") (pinfunction "2_2") (pintype "passive"))
      (node (ref "R43") (pin "2") (pinfunction "2_2") (pintype "passive"))
      (node (ref "R47") (pin "1") (pinfunction "1_1") (pintype "passive"))
      (node (ref "R48") (pin "1") (pinfunction "1_1") (pintype "passive"))
      (node (ref "R49") (pin "1") (pinfunction "1_1") (pintype "passive"))
      (node (ref "R5") (pin "1") (pinfunction "1_1") (pintype "passive"))
      (node (ref "R50") (pin "1") (pinfunction "1_1") (pintype "passive"))
      (node (ref "R51") (pin "1") (pinfunction "1_1") (pintype "passive"))
      (node (ref "RN1") (pin "1") (pinfunction "1_1") (pintype "passive"))
      (node (ref "RN2") (pin "1") (pinfunction "1_1") (pintype "passive"))
      (node (ref "ROOD") (pin "1") (pinfunction "GND_1") (pintype "power_in"))
      (node (ref "ULN1") (pin "9") (pinfunction "9_9") (pintype "bidirectional"))
      (node (ref "ULN2") (pin "9") (pinfunction "9_9") (pintype "bidirectional"))
      (node (ref "X4") (pin "1") (pinfunction "KL_1") (pintype "passive"))
    )
    (net (code "21") (name "MAIN_BOARD_GND") (class "Default")
      (node (ref "BTB_CONN") (pin "4") (pinfunction "4_4") (pintype "passive"))
      (node (ref "BTB_CONN") (pin "6") (pinfunction "6_6") (pintype "passive"))
      (node (ref "J2") (pin "1") (pinfunction "1_1") (pintype "passive"))
      (node (ref "J3") (pin "1") (pinfunction "1_1") (pintype "passive"))
    )
    (net (code "22") (name "MCLR") (class "Default")
      (node (ref "JTAG") (pin "1") (pinfunction "1_1") (pintype "passive"))
      (node (ref "PIC32MX330F064H") (pin "7") (pinfunction "~{MCLR}_7") (pintype "bidirectional"))
      (node (ref "R53") (pin "1") (pinfunction "1_1") (pintype "passive"))
    )
    (net (code "23") (name "Net-(BLAUW-IREF)") (class "Default")
      (node (ref "BLAUW") (pin "27") (pinfunction "IREF_27") (pintype "input"))
      (node (ref "R5") (pin "2") (pinfunction "2_2") (pintype "passive"))
    )
    (net (code "24") (name "Net-(BLAUW-OUT0)") (class "Default")
      (node (ref "BLAUW") (pin "7") (pinfunction "OUT0_7") (pintype "output"))
      (node (ref "X1") (pin "16") (pinfunction "KL_16") (pintype "passive"))
    )
    (net (code "25") (name "Net-(BLAUW-OUT1)") (class "Default")
      (node (ref "BLAUW") (pin "8") (pinfunction "OUT1_8") (pintype "output"))
      (node (ref "X1") (pin "15") (pinfunction "KL_15") (pintype "passive"))
    )
    (net (code "26") (name "Net-(BLAUW-OUT2)") (class "Default")
      (node (ref "BLAUW") (pin "9") (pinfunction "OUT2_9") (pintype "output"))
      (node (ref "X1") (pin "14") (pinfunction "KL_14") (pintype "passive"))
    )
    (net (code "27") (name "Net-(BLAUW-OUT3)") (class "Default")
      (node (ref "BLAUW") (pin "10") (pinfunction "OUT3_10") (pintype "output"))
      (node (ref "X1") (pin "13") (pinfunction "KL_13") (pintype "passive"))
    )
    (net (code "28") (name "Net-(BLAUW-OUT4)") (class "Default")
      (node (ref "BLAUW") (pin "11") (pinfunction "OUT4_11") (pintype "output"))
      (node (ref "X1") (pin "12") (pinfunction "KL_12") (pintype "passive"))
    )
    (net (code "29") (name "Net-(BLAUW-OUT5)") (class "Default")
      (node (ref "BLAUW") (pin "12") (pinfunction "OUT5_12") (pintype "output"))
      (node (ref "X1") (pin "11") (pinfunction "KL_11") (pintype "passive"))
    )
    (net (code "30") (name "Net-(BLAUW-OUT6)") (class "Default")
      (node (ref "BLAUW") (pin "13") (pinfunction "OUT6_13") (pintype "output"))
      (node (ref "X1") (pin "10") (pinfunction "KL_10") (pintype "passive"))
    )
    (net (code "31") (name "Net-(BLAUW-OUT7)") (class "Default")
      (node (ref "BLAUW") (pin "14") (pinfunction "OUT7_14") (pintype "output"))
      (node (ref "X1") (pin "9") (pinfunction "KL_9") (pintype "passive"))
    )
    (net (code "32") (name "Net-(BLAUW-OUT8)") (class "Default")
      (node (ref "BLAUW") (pin "15") (pinfunction "OUT8_15") (pintype "output"))
      (node (ref "X1") (pin "8") (pinfunction "KL_8") (pintype "passive"))
    )
    (net (code "33") (name "Net-(BLAUW-OUT9)") (class "Default")
      (node (ref "BLAUW") (pin "16") (pinfunction "OUT9_16") (pintype "output"))
      (node (ref "X1") (pin "7") (pinfunction "KL_7") (pintype "passive"))
    )
    (net (code "34") (name "Net-(BLAUW-OUT10)") (class "Default")
      (node (ref "BLAUW") (pin "17") (pinfunction "OUT10_17") (pintype "output"))
      (node (ref "X1") (pin "6") (pinfunction "KL_6") (pintype "passive"))
    )
    (net (code "35") (name "Net-(BLAUW-OUT11)") (class "Default")
      (node (ref "BLAUW") (pin "18") (pinfunction "OUT11_18") (pintype "output"))
      (node (ref "X1") (pin "5") (pinfunction "KL_5") (pintype "passive"))
    )
    (net (code "36") (name "Net-(BLAUW-OUT12)") (class "Default")
      (node (ref "BLAUW") (pin "19") (pinfunction "OUT12_19") (pintype "output"))
      (node (ref "X1") (pin "4") (pinfunction "KL_4") (pintype "passive"))
    )
    (net (code "37") (name "Net-(BLAUW-OUT13)") (class "Default")
      (node (ref "BLAUW") (pin "20") (pinfunction "OUT13_20") (pintype "output"))
      (node (ref "X1") (pin "3") (pinfunction "KL_3") (pintype "passive"))
    )
    (net (code "38") (name "Net-(BLAUW-OUT14)") (class "Default")
      (node (ref "BLAUW") (pin "21") (pinfunction "OUT14_21") (pintype "output"))
      (node (ref "X1") (pin "2") (pinfunction "KL_2") (pintype "passive"))
    )
    (net (code "39") (name "Net-(BLAUW-OUT15)") (class "Default")
      (node (ref "BLAUW") (pin "22") (pinfunction "OUT15_22") (pintype "output"))
      (node (ref "X1") (pin "1") (pinfunction "KL_1") (pintype "passive"))
    )
    (net (code "40") (name "Net-(C12-Pad1)") (class "Default")
      (node (ref "C12") (pin "1") (pinfunction "1_1") (pintype "passive"))
      (node (ref "R56") (pin "1") (pinfunction "1_1") (pintype "passive"))
    )
    (net (code "41") (name "Net-(C13-Pad1)") (class "Default")
      (node (ref "C13") (pin "1") (pinfunction "1_1") (pintype "passive"))
      (node (ref "R57") (pin "1") (pinfunction "1_1") (pintype "passive"))
    )
    (net (code "42") (name "Net-(C14-Pad1)") (class "Default")
      (node (ref "C14") (pin "1") (pinfunction "1_1") (pintype "passive"))
      (node (ref "R8") (pin "1") (pinfunction "1_1") (pintype "passive"))
    )
    (net (code "43") (name "Net-(C15-Pad1)") (class "Default")
      (node (ref "C15") (pin "1") (pinfunction "1_1") (pintype "passive"))
      (node (ref "R58") (pin "1") (pinfunction "1_1") (pintype "passive"))
    )
    (net (code "44") (name "Net-(C25-Pad1)") (class "Default")
      (node (ref "C25") (pin "1") (pinfunction "1_1") (pintype "passive"))
      (node (ref "J4") (pin "1") (pinfunction "1_1") (pintype "passive"))
    )
    (net (code "45") (name "Net-(C26-Pad1)") (class "Default")
      (node (ref "C26") (pin "1") (pinfunction "1_1") (pintype "passive"))
      (node (ref "R54") (pin "1") (pinfunction "1_1") (pintype "passive"))
    )
    (net (code "46") (name "Net-(C27-Pad1)") (class "Default")
      (node (ref "C27") (pin "1") (pinfunction "1_1") (pintype "passive"))
      (node (ref "R55") (pin "1") (pinfunction "1_1") (pintype "passive"))
    )
    (net (code "47") (name "Net-(C29-Pad1)") (class "Default")
      (node (ref "C29") (pin "1") (pinfunction "1_1") (pintype "passive"))
      (node (ref "R60") (pin "1") (pinfunction "1_1") (pintype "passive"))
    )
    (net (code "48") (name "Net-(C30-Pad1)") (class "Default")
      (node (ref "C30") (pin "1") (pinfunction "1_1") (pintype "passive"))
      (node (ref "R61") (pin "1") (pinfunction "1_1") (pintype "passive"))
    )
    (net (code "49") (name "Net-(GROEN-IREF)") (class "Default")
      (node (ref "GROEN") (pin "27") (pinfunction "IREF_27") (pintype "input"))
      (node (ref "R4") (pin "2") (pinfunction "2_2") (pintype "passive"))
    )
    (net (code "50") (name "Net-(GROEN-OUT0)") (class "Default")
      (node (ref "GROEN") (pin "7") (pinfunction "OUT0_7") (pintype "output"))
      (node (ref "X2") (pin "16") (pinfunction "KL_16") (pintype "passive"))
    )
    (net (code "51") (name "Net-(GROEN-OUT1)") (class "Default")
      (node (ref "GROEN") (pin "8") (pinfunction "OUT1_8") (pintype "output"))
      (node (ref "X2") (pin "15") (pinfunction "KL_15") (pintype "passive"))
    )
    (net (code "52") (name "Net-(GROEN-OUT2)") (class "Default")
      (node (ref "GROEN") (pin "9") (pinfunction "OUT2_9") (pintype "output"))
      (node (ref "X2") (pin "14") (pinfunction "KL_14") (pintype "passive"))
    )
    (net (code "53") (name "Net-(GROEN-OUT3)") (class "Default")
      (node (ref "GROEN") (pin "10") (pinfunction "OUT3_10") (pintype "output"))
      (node (ref "X2") (pin "13") (pinfunction "KL_13") (pintype "passive"))
    )
    (net (code "54") (name "Net-(GROEN-OUT4)") (class "Default")
      (node (ref "GROEN") (pin "11") (pinfunction "OUT4_11") (pintype "output"))
      (node (ref "X2") (pin "12") (pinfunction "KL_12") (pintype "passive"))
    )
    (net (code "55") (name "Net-(GROEN-OUT5)") (class "Default")
      (node (ref "GROEN") (pin "12") (pinfunction "OUT5_12") (pintype "output"))
      (node (ref "X2") (pin "11") (pinfunction "KL_11") (pintype "passive"))
    )
    (net (code "56") (name "Net-(GROEN-OUT6)") (class "Default")
      (node (ref "GROEN") (pin "13") (pinfunction "OUT6_13") (pintype "output"))
      (node (ref "X2") (pin "10") (pinfunction "KL_10") (pintype "passive"))
    )
    (net (code "57") (name "Net-(GROEN-OUT7)") (class "Default")
      (node (ref "GROEN") (pin "14") (pinfunction "OUT7_14") (pintype "output"))
      (node (ref "X2") (pin "9") (pinfunction "KL_9") (pintype "passive"))
    )
    (net (code "58") (name "Net-(GROEN-OUT8)") (class "Default")
      (node (ref "GROEN") (pin "15") (pinfunction "OUT8_15") (pintype "output"))
      (node (ref "X2") (pin "8") (pinfunction "KL_8") (pintype "passive"))
    )
    (net (code "59") (name "Net-(GROEN-OUT9)") (class "Default")
      (node (ref "GROEN") (pin "16") (pinfunction "OUT9_16") (pintype "output"))
      (node (ref "X2") (pin "7") (pinfunction "KL_7") (pintype "passive"))
    )
    (net (code "60") (name "Net-(GROEN-OUT10)") (class "Default")
      (node (ref "GROEN") (pin "17") (pinfunction "OUT10_17") (pintype "output"))
      (node (ref "X2") (pin "6") (pinfunction "KL_6") (pintype "passive"))
    )
    (net (code "61") (name "Net-(GROEN-OUT11)") (class "Default")
      (node (ref "GROEN") (pin "18") (pinfunction "OUT11_18") (pintype "output"))
      (node (ref "X2") (pin "5") (pinfunction "KL_5") (pintype "passive"))
    )
    (net (code "62") (name "Net-(GROEN-OUT12)") (class "Default")
      (node (ref "GROEN") (pin "19") (pinfunction "OUT12_19") (pintype "output"))
      (node (ref "X2") (pin "4") (pinfunction "KL_4") (pintype "passive"))
    )
    (net (code "63") (name "Net-(GROEN-OUT13)") (class "Default")
      (node (ref "GROEN") (pin "20") (pinfunction "OUT13_20") (pintype "output"))
      (node (ref "X2") (pin "3") (pinfunction "KL_3") (pintype "passive"))
    )
    (net (code "64") (name "Net-(GROEN-OUT14)") (class "Default")
      (node (ref "GROEN") (pin "21") (pinfunction "OUT14_21") (pintype "output"))
      (node (ref "X2") (pin "2") (pinfunction "KL_2") (pintype "passive"))
    )
    (net (code "65") (name "Net-(GROEN-OUT15)") (class "Default")
      (node (ref "GROEN") (pin "22") (pinfunction "OUT15_22") (pintype "output"))
      (node (ref "X2") (pin "1") (pinfunction "KL_1") (pintype "passive"))
    )
    (net (code "66") (name "Net-(GROEN-SOUT)") (class "Default")
      (node (ref "GROEN") (pin "24") (pinfunction "SOUT_24") (pintype "output"))
      (node (ref "R2") (pin "1") (pinfunction "1_1") (pintype "passive"))
    )
    (net (code "67") (name "Net-(J4-Pad2)") (class "Default")
      (node (ref "J4") (pin "2") (pinfunction "2_2") (pintype "passive"))
      (node (ref "R52") (pin "2") (pinfunction "2_2") (pintype "passive"))
      (node (ref "R53") (pin "2") (pinfunction "2_2") (pintype "passive"))
    )
    (net (code "68") (name "Net-(PIC32MX330F064H-AN17{slash}C1INC{slash}RPG7{slash}PMA4{slash}RG7)") (class "Default")
      (node (ref "PIC32MX330F064H") (pin "5") (pinfunction "AN17/C1INC/RPG7/PMA4/RG7_5") (pintype "bidirectional"))
      (node (ref "R9") (pin "2") (pinfunction "2_2") (pintype "passive"))
    )
    (net (code "69") (name "Net-(PIC32MX330F064H-AN20{slash}PMD2{slash}RE2)") (class "Default")
      (node (ref "PIC32MX330F064H") (pin "62") (pinfunction "AN20/PMD2/RE2_62") (pintype "bidirectional"))
      (node (ref "ULN2") (pin "7") (pinfunction "7_7") (pintype "bidirectional"))
    )
    (net (code "70") (name "Net-(PIC32MX330F064H-AN24{slash}RPD1{slash}RD1)") (class "Default")
      (node (ref "PIC32MX330F064H") (pin "49") (pinfunction "AN24/RPD1/RD1_49") (pintype "bidirectional"))
      (node (ref "ULN1") (pin "2") (pinfunction "2_2") (pintype "bidirectional"))
    )
    (net (code "71") (name "Net-(PIC32MX330F064H-AN25{slash}RPD2{slash}RD2)") (class "Default")
      (node (ref "PIC32MX330F064H") (pin "50") (pinfunction "AN25/RPD2/RD2_50") (pintype "bidirectional"))
      (node (ref "ULN1") (pin "3") (pinfunction "3_3") (pintype "bidirectional"))
    )
    (net (code "72") (name "Net-(PIC32MX330F064H-AN26{slash}RPD3{slash}RD3)") (class "Default")
      (node (ref "PIC32MX330F064H") (pin "51") (pinfunction "AN26/RPD3/RD3_51") (pintype "bidirectional"))
      (node (ref "ULN1") (pin "4") (pinfunction "4_4") (pintype "bidirectional"))
    )
    (net (code "73") (name "Net-(PIC32MX330F064H-OSC1{slash}CLKI{slash}RC12)") (class "Default")
      (node (ref "C17") (pin "2") (pinfunction "2_2") (pintype "passive"))
      (node (ref "PIC32MX330F064H") (pin "39") (pinfunction "OSC1/CLKI/RC12_39") (pintype "bidirectional"))
      (node (ref "XTAL") (pin "2") (pinfunction "2_2") (pintype "passive"))
    )
    (net (code "74") (name "Net-(PIC32MX330F064H-OSC2{slash}CLKO{slash}RC15)") (class "Default")
      (node (ref "C18") (pin "2") (pinfunction "2_2") (pintype "passive"))
      (node (ref "PIC32MX330F064H") (pin "40") (pinfunction "OSC2/CLKO/RC15_40") (pintype "bidirectional"))
      (node (ref "XTAL") (pin "1") (pinfunction "1_1") (pintype "passive"))
    )
    (net (code "75") (name "Net-(PIC32MX330F064H-PMD0{slash}RE0)") (class "Default")
      (node (ref "PIC32MX330F064H") (pin "60") (pinfunction "PMD0/RE0_60") (pintype "bidirectional"))
      (node (ref "ULN2") (pin "5") (pinfunction "5_5") (pintype "bidirectional"))
    )
    (net (code "76") (name "Net-(PIC32MX330F064H-PMD1{slash}RE1)") (class "Default")
      (node (ref "PIC32MX330F064H") (pin "61") (pinfunction "PMD1/RE1_61") (pintype "bidirectional"))
      (node (ref "ULN2") (pin "6") (pinfunction "6_6") (pintype "bidirectional"))
    )
    (net (code "77") (name "Net-(PIC32MX330F064H-RD6)") (class "Default")
      (node (ref "PIC32MX330F064H") (pin "54") (pinfunction "RD6_54") (pintype "bidirectional"))
      (node (ref "ULN1") (pin "7") (pinfunction "7_7") (pintype "bidirectional"))
    )
    (net (code "78") (name "Net-(PIC32MX330F064H-RD7)") (class "Default")
      (node (ref "PIC32MX330F064H") (pin "55") (pinfunction "RD7_55") (pintype "bidirectional"))
      (node (ref "ULN1") (pin "8") (pinfunction "8_8") (pintype "bidirectional"))
    )
    (net (code "79") (name "Net-(PIC32MX330F064H-RPD0{slash}RD0)") (class "Default")
      (node (ref "PIC32MX330F064H") (pin "46") (pinfunction "RPD0/RD0_46") (pintype "bidirectional"))
      (node (ref "ULN1") (pin "1") (pinfunction "1_1") (pintype "bidirectional"))
    )
    (net (code "80") (name "Net-(PIC32MX330F064H-RPD4{slash}PMWR{slash}RD4)") (class "Default")
      (node (ref "PIC32MX330F064H") (pin "52") (pinfunction "RPD4/PMWR/RD4_52") (pintype "bidirectional"))
      (node (ref "ULN1") (pin "5") (pinfunction "5_5") (pintype "bidirectional"))
    )
    (net (code "81") (name "Net-(PIC32MX330F064H-RPD5{slash}PMRD{slash}RD5)") (class "Default")
      (node (ref "PIC32MX330F064H") (pin "53") (pinfunction "RPD5/PMRD/RD5_53") (pintype "bidirectional"))
      (node (ref "ULN1") (pin "6") (pinfunction "6_6") (pintype "bidirectional"))
    )
    (net (code "82") (name "Net-(PIC32MX330F064H-RPD8{slash}RTCC{slash}RD8)") (class "Default")
      (node (ref "PIC32MX330F064H") (pin "42") (pinfunction "RPD8/RTCC/RD8_42") (pintype "bidirectional"))
      (node (ref "ULN2") (pin "1") (pinfunction "1_1") (pintype "bidirectional"))
    )
    (net (code "83") (name "Net-(PIC32MX330F064H-RPD9{slash}RD9)") (class "Default")
      (node (ref "PIC32MX330F064H") (pin "43") (pinfunction "RPD9/RD9_43") (pintype "bidirectional"))
      (node (ref "ULN2") (pin "2") (pinfunction "2_2") (pintype "bidirectional"))
    )
    (net (code "84") (name "Net-(PIC32MX330F064H-RPD10{slash}PMCS2{slash}RD10)") (class "Default")
      (node (ref "PIC32MX330F064H") (pin "44") (pinfunction "RPD10/PMCS2/RD10_44") (pintype "bidirectional"))
      (node (ref "ULN2") (pin "3") (pinfunction "3_3") (pintype "bidirectional"))
    )
    (net (code "85") (name "Net-(PIC32MX330F064H-RPD11{slash}PMCS1{slash}RD11)") (class "Default")
      (node (ref "PIC32MX330F064H") (pin "45") (pinfunction "RPD11/PMCS1/RD11_45") (pintype "bidirectional"))
      (node (ref "ULN2") (pin "4") (pinfunction "4_4") (pintype "bidirectional"))
    )
    (net (code "86") (name "Net-(PIC32MX330F064H-RPE3{slash}CTPLS{slash}PMD3{slash}RE3)") (class "Default")
      (node (ref "PIC32MX330F064H") (pin "63") (pinfunction "RPE3/CTPLS/PMD3/RE3_63") (pintype "bidirectional"))
      (node (ref "ULN2") (pin "8") (pinfunction "8_8") (pintype "bidirectional"))
    )
    (net (code "87") (name "Net-(PIC32MX330F064H-VCAP)") (class "Default")
      (node (ref "C24") (pin "1") (pinfunction "1_1") (pintype "passive"))
      (node (ref "PIC32MX330F064H") (pin "56") (pinfunction "VCAP_56") (pintype "power_in"))
    )
    (net (code "88") (name "Net-(Q1-G)") (class "Default")
      (node (ref "Q1") (pin "1") (pinfunction "G_1") (pintype "passive"))
      (node (ref "R10") (pin "1") (pinfunction "1_1") (pintype "passive"))
      (node (ref "R11") (pin "1") (pinfunction "1_1") (pintype "passive"))
    )
    (net (code "89") (name "Net-(Q2-G)") (class "Default")
      (node (ref "Q2") (pin "1") (pinfunction "G_1") (pintype "passive"))
      (node (ref "R12") (pin "1") (pinfunction "1_1") (pintype "passive"))
      (node (ref "R13") (pin "1") (pinfunction "1_1") (pintype "passive"))
    )
    (net (code "90") (name "Net-(Q3-G)") (class "Default")
      (node (ref "Q3") (pin "1") (pinfunction "G_1") (pintype "passive"))
      (node (ref "R14") (pin "1") (pinfunction "1_1") (pintype "passive"))
      (node (ref "R15") (pin "1") (pinfunction "1_1") (pintype "passive"))
    )
    (net (code "91") (name "Net-(Q4-G)") (class "Default")
      (node (ref "Q4") (pin "1") (pinfunction "G_1") (pintype "passive"))
      (node (ref "R16") (pin "1") (pinfunction "1_1") (pintype "passive"))
      (node (ref "R17") (pin "1") (pinfunction "1_1") (pintype "passive"))
    )
    (net (code "92") (name "Net-(Q5-G)") (class "Default")
      (node (ref "Q5") (pin "1") (pinfunction "G_1") (pintype "passive"))
      (node (ref "R18") (pin "1") (pinfunction "1_1") (pintype "passive"))
      (node (ref "R19") (pin "1") (pinfunction "1_1") (pintype "passive"))
    )
    (net (code "93") (name "Net-(Q6-G)") (class "Default")
      (node (ref "Q6") (pin "1") (pinfunction "G_1") (pintype "passive"))
      (node (ref "R20") (pin "1") (pinfunction "1_1") (pintype "passive"))
      (node (ref "R21") (pin "1") (pinfunction "1_1") (pintype "passive"))
    )
    (net (code "94") (name "Net-(Q7-G)") (class "Default")
      (node (ref "Q7") (pin "1") (pinfunction "G_1") (pintype "passive"))
      (node (ref "R22") (pin "1") (pinfunction "1_1") (pintype "passive"))
      (node (ref "R23") (pin "1") (pinfunction "1_1") (pintype "passive"))
    )
    (net (code "95") (name "Net-(Q8-G)") (class "Default")
      (node (ref "Q8") (pin "1") (pinfunction "G_1") (pintype "passive"))
      (node (ref "R24") (pin "1") (pinfunction "1_1") (pintype "passive"))
      (node (ref "R25") (pin "1") (pinfunction "1_1") (pintype "passive"))
    )
    (net (code "96") (name "Net-(Q9-G)") (class "Default")
      (node (ref "Q9") (pin "1") (pinfunction "G_1") (pintype "passive"))
      (node (ref "R26") (pin "1") (pinfunction "1_1") (pintype "passive"))
      (node (ref "R27") (pin "1") (pinfunction "1_1") (pintype "passive"))
    )
    (net (code "97") (name "Net-(Q10-G)") (class "Default")
      (node (ref "Q10") (pin "1") (pinfunction "G_1") (pintype "passive"))
      (node (ref "R28") (pin "1") (pinfunction "1_1") (pintype "passive"))
      (node (ref "R29") (pin "1") (pinfunction "1_1") (pintype "passive"))
    )
    (net (code "98") (name "Net-(Q11-G)") (class "Default")
      (node (ref "Q11") (pin "1") (pinfunction "G_1") (pintype "passive"))
      (node (ref "R30") (pin "1") (pinfunction "1_1") (pintype "passive"))
      (node (ref "R31") (pin "1") (pinfunction "1_1") (pintype "passive"))
    )
    (net (code "99") (name "Net-(Q12-G)") (class "Default")
      (node (ref "Q12") (pin "1") (pinfunction "G_1") (pintype "passive"))
      (node (ref "R32") (pin "1") (pinfunction "1_1") (pintype "passive"))
      (node (ref "R33") (pin "1") (pinfunction "1_1") (pintype "passive"))
    )
    (net (code "100") (name "Net-(Q13-G)") (class "Default")
      (node (ref "Q13") (pin "1") (pinfunction "G_1") (pintype "passive"))
      (node (ref "R34") (pin "1") (pinfunction "1_1") (pintype "passive"))
      (node (ref "R35") (pin "1") (pinfunction "1_1") (pintype "passive"))
    )
    (net (code "101") (name "Net-(Q14-G)") (class "Default")
      (node (ref "Q14") (pin "1") (pinfunction "G_1") (pintype "passive"))
      (node (ref "R36") (pin "1") (pinfunction "1_1") (pintype "passive"))
      (node (ref "R37") (pin "1") (pinfunction "1_1") (pintype "passive"))
    )
    (net (code "102") (name "Net-(Q15-G)") (class "Default")
      (node (ref "Q15") (pin "1") (pinfunction "G_1") (pintype "passive"))
      (node (ref "R38") (pin "1") (pinfunction "1_1") (pintype "passive"))
      (node (ref "R39") (pin "1") (pinfunction "1_1") (pintype "passive"))
    )
    (net (code "103") (name "Net-(Q16-G)") (class "Default")
      (node (ref "Q16") (pin "1") (pinfunction "G_1") (pintype "passive"))
      (node (ref "R40") (pin "1") (pinfunction "1_1") (pintype "passive"))
      (node (ref "R41") (pin "1") (pinfunction "1_1") (pintype "passive"))
    )
    (net (code "104") (name "Net-(ROOD-IREF)") (class "Default")
      (node (ref "R3") (pin "2") (pinfunction "2_2") (pintype "passive"))
      (node (ref "ROOD") (pin "27") (pinfunction "IREF_27") (pintype "input"))
    )
    (net (code "105") (name "Net-(ROOD-OUT0)") (class "Default")
      (node (ref "ROOD") (pin "7") (pinfunction "OUT0_7") (pintype "output"))
      (node (ref "X3") (pin "16") (pinfunction "KL_16") (pintype "passive"))
    )
    (net (code "106") (name "Net-(ROOD-OUT1)") (class "Default")
      (node (ref "ROOD") (pin "8") (pinfunction "OUT1_8") (pintype "output"))
      (node (ref "X3") (pin "15") (pinfunction "KL_15") (pintype "passive"))
    )
    (net (code "107") (name "Net-(ROOD-OUT2)") (class "Default")
      (node (ref "ROOD") (pin "9") (pinfunction "OUT2_9") (pintype "output"))
      (node (ref "X3") (pin "14") (pinfunction "KL_14") (pintype "passive"))
    )
    (net (code "108") (name "Net-(ROOD-OUT3)") (class "Default")
      (node (ref "ROOD") (pin "10") (pinfunction "OUT3_10") (pintype "output"))
      (node (ref "X3") (pin "13") (pinfunction "KL_13") (pintype "passive"))
    )
    (net (code "109") (name "Net-(ROOD-OUT4)") (class "Default")
      (node (ref "ROOD") (pin "11") (pinfunction "OUT4_11") (pintype "output"))
      (node (ref "X3") (pin "12") (pinfunction "KL_12") (pintype "passive"))
    )
    (net (code "110") (name "Net-(ROOD-OUT5)") (class "Default")
      (node (ref "ROOD") (pin "12") (pinfunction "OUT5_12") (pintype "output"))
      (node (ref "X3") (pin "11") (pinfunction "KL_11") (pintype "passive"))
    )
    (net (code "111") (name "Net-(ROOD-OUT6)") (class "Default")
      (node (ref "ROOD") (pin "13") (pinfunction "OUT6_13") (pintype "output"))
      (node (ref "X3") (pin "10") (pinfunction "KL_10") (pintype "passive"))
    )
    (net (code "112") (name "Net-(ROOD-OUT7)") (class "Default")
      (node (ref "ROOD") (pin "14") (pinfunction "OUT7_14") (pintype "output"))
      (node (ref "X3") (pin "9") (pinfunction "KL_9") (pintype "passive"))
    )
    (net (code "113") (name "Net-(ROOD-OUT8)") (class "Default")
      (node (ref "ROOD") (pin "15") (pinfunction "OUT8_15") (pintype "output"))
      (node (ref "X3") (pin "8") (pinfunction "KL_8") (pintype "passive"))
    )
    (net (code "114") (name "Net-(ROOD-OUT9)") (class "Default")
      (node (ref "ROOD") (pin "16") (pinfunction "OUT9_16") (pintype "output"))
      (node (ref "X3") (pin "7") (pinfunction "KL_7") (pintype "passive"))
    )
    (net (code "115") (name "Net-(ROOD-OUT10)") (class "Default")
      (node (ref "ROOD") (pin "17") (pinfunction "OUT10_17") (pintype "output"))
      (node (ref "X3") (pin "6") (pinfunction "KL_6") (pintype "passive"))
    )
    (net (code "116") (name "Net-(ROOD-OUT11)") (class "Default")
      (node (ref "ROOD") (pin "18") (pinfunction "OUT11_18") (pintype "output"))
      (node (ref "X3") (pin "5") (pinfunction "KL_5") (pintype "passive"))
    )
    (net (code "117") (name "Net-(ROOD-OUT12)") (class "Default")
      (node (ref "ROOD") (pin "19") (pinfunction "OUT12_19") (pintype "output"))
      (node (ref "X3") (pin "4") (pinfunction "KL_4") (pintype "passive"))
    )
    (net (code "118") (name "Net-(ROOD-OUT13)") (class "Default")
      (node (ref "ROOD") (pin "20") (pinfunction "OUT13_20") (pintype "output"))
      (node (ref "X3") (pin "3") (pinfunction "KL_3") (pintype "passive"))
    )
    (net (code "119") (name "Net-(ROOD-OUT14)") (class "Default")
      (node (ref "ROOD") (pin "21") (pinfunction "OUT14_21") (pintype "output"))
      (node (ref "X3") (pin "2") (pinfunction "KL_2") (pintype "passive"))
    )
    (net (code "120") (name "Net-(ROOD-OUT15)") (class "Default")
      (node (ref "ROOD") (pin "22") (pinfunction "OUT15_22") (pintype "output"))
      (node (ref "X3") (pin "1") (pinfunction "KL_1") (pintype "passive"))
    )
    (net (code "121") (name "Net-(ROOD-SOUT)") (class "Default")
      (node (ref "R1") (pin "1") (pinfunction "1_1") (pintype "passive"))
      (node (ref "ROOD") (pin "24") (pinfunction "SOUT_24") (pintype "output"))
    )
    (net (code "122") (name "PGEC1") (class "Default")
      (node (ref "JTAG") (pin "5") (pinfunction "5_5") (pintype "passive"))
      (node (ref "PIC32MX330F064H") (pin "15") (pinfunction "PGEC1/VREF-/CVREF-/AN1/RPB1/CTED12/RB1_15") (pintype "bidirectional"))
    )
    (net (code "123") (name "PGED1") (class "Default")
      (node (ref "JTAG") (pin "4") (pinfunction "4_4") (pintype "passive"))
      (node (ref "PIC32MX330F064H") (pin "16") (pinfunction "PGED1/VREF+/CVREF+/AN0/RPB0/PMA6/RB0_16") (pintype "bidirectional"))
    )
    (net (code "124") (name "PGM") (class "Default")
      (node (ref "JTAG") (pin "6") (pinfunction "6_6") (pintype "passive"))
    )
    (net (code "125") (name "ROW_0") (class "Default")
      (node (ref "R11") (pin "2") (pinfunction "2_2") (pintype "passive"))
      (node (ref "ULN1") (pin "11") (pinfunction "11_11") (pintype "bidirectional"))
    )
    (net (code "126") (name "ROW_1") (class "Default")
      (node (ref "R13") (pin "2") (pinfunction "2_2") (pintype "passive"))
      (node (ref "ULN1") (pin "12") (pinfunction "12_12") (pintype "bidirectional"))
    )
    (net (code "127") (name "ROW_2") (class "Default")
      (node (ref "R15") (pin "2") (pinfunction "2_2") (pintype "passive"))
      (node (ref "ULN1") (pin "13") (pinfunction "13_13") (pintype "bidirectional"))
    )
    (net (code "128") (name "ROW_3") (class "Default")
      (node (ref "R17") (pin "2") (pinfunction "2_2") (pintype "passive"))
      (node (ref "ULN1") (pin "14") (pinfunction "14_14") (pintype "bidirectional"))
    )
    (net (code "129") (name "ROW_4") (class "Default")
      (node (ref "R19") (pin "2") (pinfunction "2_2") (pintype "passive"))
      (node (ref "ULN1") (pin "15") (pinfunction "15_15") (pintype "bidirectional"))
    )
    (net (code "130") (name "ROW_5") (class "Default")
      (node (ref "R21") (pin "2") (pinfunction "2_2") (pintype "passive"))
      (node (ref "ULN1") (pin "16") (pinfunction "16_16") (pintype "bidirectional"))
    )
    (net (code "131") (name "ROW_6") (class "Default")
      (node (ref "R23") (pin "2") (pinfunction "2_2") (pintype "passive"))
      (node (ref "ULN1") (pin "17") (pinfunction "17_17") (pintype "bidirectional"))
    )
    (net (code "132") (name "ROW_7") (class "Default")
      (node (ref "R25") (pin "2") (pinfunction "2_2") (pintype "passive"))
      (node (ref "ULN1") (pin "18") (pinfunction "18_18") (pintype "bidirectional"))
    )
    (net (code "133") (name "ROW_8") (class "Default")
      (node (ref "R27") (pin "2") (pinfunction "2_2") (pintype "passive"))
      (node (ref "ULN2") (pin "11") (pinfunction "11_11") (pintype "bidirectional"))
    )
    (net (code "134") (name "ROW_9") (class "Default")
      (node (ref "R29") (pin "2") (pinfunction "2_2") (pintype "passive"))
      (node (ref "ULN2") (pin "12") (pinfunction "12_12") (pintype "bidirectional"))
    )
    (net (code "135") (name "ROW_10") (class "Default")
      (node (ref "R31") (pin "2") (pinfunction "2_2") (pintype "passive"))
      (node (ref "ULN2") (pin "13") (pinfunction "13_13") (pintype "bidirectional"))
    )
    (net (code "136") (name "ROW_11") (class "Default")
      (node (ref "R33") (pin "2") (pinfunction "2_2") (pintype "passive"))
      (node (ref "ULN2") (pin "14") (pinfunction "14_14") (pintype "bidirectional"))
    )
    (net (code "137") (name "ROW_12") (class "Default")
      (node (ref "R35") (pin "2") (pinfunction "2_2") (pintype "passive"))
      (node (ref "ULN2") (pin "15") (pinfunction "15_15") (pintype "bidirectional"))
    )
    (net (code "138") (name "ROW_13") (class "Default")
      (node (ref "R37") (pin "2") (pinfunction "2_2") (pintype "passive"))
      (node (ref "ULN2") (pin "16") (pinfunction "16_16") (pintype "bidirectional"))
    )
    (net (code "139") (name "ROW_14") (class "Default")
      (node (ref "R39") (pin "2") (pinfunction "2_2") (pintype "passive"))
      (node (ref "ULN2") (pin "17") (pinfunction "17_17") (pintype "bidirectional"))
    )
    (net (code "140") (name "ROW_15") (class "Default")
      (node (ref "R41") (pin "2") (pinfunction "2_2") (pintype "passive"))
      (node (ref "ULN2") (pin "18") (pinfunction "18_18") (pintype "bidirectional"))
    )
    (net (code "141") (name "RS485_A") (class "Default")
      (node (ref "BTB_CONN") (pin "9") (pinfunction "9_9") (pintype "passive"))
      (node (ref "MAX3485") (pin "6") (pinfunction "A_6") (pintype "bidirectional"))
      (node (ref "R44") (pin "2") (pinfunction "2_2") (pintype "passive"))
      (node (ref "R45") (pin "1") (pinfunction "1_1") (pintype "passive"))
    )
    (net (code "142") (name "RS485_ADR_0") (class "Default")
      (node (ref "PIC32MX330F064H") (pin "14") (pinfunction "PGEC3/AN2/C2INB/RPB2/CTED13/RB2_14") (pintype "bidirectional"))
      (node (ref "R51") (pin "2") (pinfunction "2_2") (pintype "passive"))
      (node (ref "SW1") (pin "10") (pinfunction "10_10") (pintype "passive"))
    )
    (net (code "143") (name "RS485_ADR_1") (class "Default")
      (node (ref "PIC32MX330F064H") (pin "32") (pinfunction "RPF5/SCL2/PMA8/RF5_32") (pintype "bidirectional"))
      (node (ref "R50") (pin "2") (pinfunction "2_2") (pintype "passive"))
      (node (ref "SW1") (pin "9") (pinfunction "9_9") (pintype "passive"))
    )
    (net (code "144") (name "RS485_ADR_2") (class "Default")
      (node (ref "PIC32MX330F064H") (pin "27") (pinfunction "TCK/AN12/PMA11/RB12_27") (pintype "bidirectional"))
      (node (ref "R49") (pin "2") (pinfunction "2_2") (pintype "passive"))
      (node (ref "SW1") (pin "8") (pinfunction "8_8") (pintype "passive"))
    )
    (net (code "145") (name "RS485_ADR_3") (class "Default")
      (node (ref "PIC32MX330F064H") (pin "28") (pinfunction "TDI/AN13/PMA10/RB13_28") (pintype "bidirectional"))
      (node (ref "R48") (pin "2") (pinfunction "2_2") (pintype "passive"))
      (node (ref "SW1") (pin "7") (pinfunction "7_7") (pintype "passive"))
    )
    (net (code "146") (name "RS485_ADR_4") (class "Default")
      (node (ref "PIC32MX330F064H") (pin "31") (pinfunction "RPF4/SDA2/PMA9/RF4_31") (pintype "bidirectional"))
      (node (ref "R47") (pin "2") (pinfunction "2_2") (pintype "passive"))
      (node (ref "SW1") (pin "6") (pinfunction "6_6") (pintype "passive"))
    )
    (net (code "147") (name "RS485_B") (class "Default")
      (node (ref "BTB_CONN") (pin "11") (pinfunction "11_11") (pintype "passive"))
      (node (ref "MAX3485") (pin "7") (pinfunction "B_7") (pintype "bidirectional"))
      (node (ref "R43") (pin "1") (pinfunction "1_1") (pintype "passive"))
      (node (ref "R45") (pin "2") (pinfunction "2_2") (pintype "passive"))
    )
    (net (code "148") (name "RS485_CABLE_GND") (class "Default")
      (node (ref "BTB_CONN") (pin "10") (pinfunction "10_10") (pintype "passive"))
      (node (ref "J1") (pin "2") (pinfunction "2_2") (pintype "passive"))
    )
    (net (code "149") (name "RS485_DI") (class "Default")
      (node (ref "MAX3485") (pin "4") (pinfunction "DI_4") (pintype "bidirectional"))
      (node (ref "PIC32MX330F064H") (pin "13") (pinfunction "PGED3/AN3/C2INA/RPB3/RB3_13") (pintype "bidirectional"))
    )
    (net (code "150") (name "RS485_DIR") (class "Default")
      (node (ref "MAX3485") (pin "2") (pinfunction "/RE_2") (pintype "bidirectional"))
      (node (ref "MAX3485") (pin "3") (pinfunction "DE_3") (pintype "bidirectional"))
      (node (ref "PIC32MX330F064H") (pin "18") (pinfunction "PGED2/AN7/RPB7/CTED3//RB7_18") (pintype "bidirectional"))
      (node (ref "R42") (pin "1") (pinfunction "1_1") (pintype "passive"))
    )
    (net (code "151") (name "RS485_RO") (class "Default")
      (node (ref "MAX3485") (pin "1") (pinfunction "RO_1") (pintype "bidirectional"))
      (node (ref "PIC32MX330F064H") (pin "6") (pinfunction "AN18/C2IND/RPG8/PMA3/RG8_6") (pintype "bidirectional"))
      (node (ref "R46") (pin "1") (pinfunction "1_1") (pintype "passive"))
    )
    (net (code "152") (name "SCK1") (class "Default")
      (node (ref "BTB_CONN") (pin "7") (pinfunction "7_7") (pintype "passive"))
      (node (ref "PIC32MX330F064H") (pin "35") (pinfunction "RPF6/SCK1/INT0/RF6_35") (pintype "bidirectional"))
      (node (ref "R55") (pin "2") (pinfunction "2_2") (pintype "passive"))
    )
    (net (code "153") (name "SDI1") (class "Default")
      (node (ref "BTB_CONN") (pin "5") (pinfunction "5_5") (pintype "passive"))
      (node (ref "PIC32MX330F064H") (pin "34") (pinfunction "RPF2/RF2_34") (pintype "bidirectional"))
      (node (ref "R54") (pin "2") (pinfunction "2_2") (pintype "passive"))
    )
    (net (code "154") (name "SDO1") (class "Default")
      (node (ref "BTB_CONN") (pin "3") (pinfunction "3_3") (pintype "passive"))
      (node (ref "PIC32MX330F064H") (pin "33") (pinfunction "RPF3/RF3_33") (pintype "bidirectional"))
    )
    (net (code "155") (name "TLC_BLANK") (class "Default")
      (node (ref "BLAUW") (pin "2") (pinfunction "BLANK_2") (pintype "input"))
      (node (ref "GROEN") (pin "2") (pinfunction "BLANK_2") (pintype "input"))
      (node (ref "PIC32MX330F064H") (pin "3") (pinfunction "AN27/PMD7/RE7_3") (pintype "bidirectional"))
      (node (ref "R6") (pin "1") (pinfunction "1_1") (pintype "passive"))
      (node (ref "R61") (pin "2") (pinfunction "2_2") (pintype "passive"))
      (node (ref "ROOD") (pin "2") (pinfunction "BLANK_2") (pintype "input"))
    )
    (net (code "156") (name "TLC_B_OUT") (class "Default")
      (node (ref "BLAUW") (pin "24") (pinfunction "SOUT_24") (pintype "output"))
    )
    (net (code "157") (name "TLC_DCPRG") (class "Default")
      (node (ref "BLAUW") (pin "26") (pinfunction "DCPRG_26") (pintype "input"))
      (node (ref "GROEN") (pin "26") (pinfunction "DCPRG_26") (pintype "input"))
      (node (ref "PIC32MX330F064H") (pin "11") (pinfunction "AN5/C1INA/RPB5/RB5_11") (pintype "bidirectional"))
      (node (ref "R57") (pin "2") (pinfunction "2_2") (pintype "passive"))
      (node (ref "ROOD") (pin "26") (pinfunction "DCPRG_26") (pintype "input"))
    )
    (net (code "158") (name "TLC_GSCLK") (class "Default")
      (node (ref "BLAUW") (pin "25") (pinfunction "GSCLK_25") (pintype "input"))
      (node (ref "GROEN") (pin "25") (pinfunction "GSCLK_25") (pintype "input"))
      (node (ref "PIC32MX330F064H") (pin "1") (pinfunction "AN22/RPE5/PMD5/RE5_1") (pintype "bidirectional"))
      (node (ref "R56") (pin "2") (pinfunction "2_2") (pintype "passive"))
      (node (ref "ROOD") (pin "25") (pinfunction "GSCLK_25") (pintype "input"))
    )
    (net (code "159") (name "TLC_G_OUT") (class "Default")
      (node (ref "BLAUW") (pin "5") (pinfunction "SIN_5") (pintype "input"))
      (node (ref "R2") (pin "2") (pinfunction "2_2") (pintype "passive"))
    )
    (net (code "160") (name "TLC_R_OUT") (class "Default")
      (node (ref "GROEN") (pin "5") (pinfunction "SIN_5") (pintype "input"))
      (node (ref "R1") (pin "2") (pinfunction "2_2") (pintype "passive"))
    )
    (net (code "161") (name "TLC_R_SIN") (class "Default")
      (node (ref "R9") (pin "1") (pinfunction "1_1") (pintype "passive"))
      (node (ref "ROOD") (pin "5") (pinfunction "SIN_5") (pintype "input"))
    )
    (net (code "162") (name "TLC_SCLK") (class "Default")
      (node (ref "BLAUW") (pin "4") (pinfunction "SCLK_4") (pintype "input"))
      (node (ref "GROEN") (pin "4") (pinfunction "SCLK_4") (pintype "input"))
      (node (ref "PIC32MX330F064H") (pin "4") (pinfunction "AN16/C1IND/RPG6/SCK2/PMA5/RG6_4") (pintype "bidirectional"))
      (node (ref "R8") (pin "2") (pinfunction "2_2") (pintype "passive"))
      (node (ref "ROOD") (pin "4") (pinfunction "SCLK_4") (pintype "input"))
    )
    (net (code "163") (name "TLC_VPRG") (class "Default")
      (node (ref "BLAUW") (pin "6") (pinfunction "VPRG_6") (pintype "input"))
      (node (ref "GROEN") (pin "6") (pinfunction "VPRG_6") (pintype "input"))
      (node (ref "PIC32MX330F064H") (pin "8") (pinfunction "AN19/C2INC/RPG9/PMA2/RG9_8") (pintype "bidirectional"))
      (node (ref "R58") (pin "2") (pinfunction "2_2") (pintype "passive"))
      (node (ref "ROOD") (pin "6") (pinfunction "VPRG_6") (pintype "input"))
    )
    (net (code "164") (name "TLC_XERR") (class "Default")
      (node (ref "BLAUW") (pin "23") (pinfunction "XERR_23") (pintype "open_collector"))
      (node (ref "GROEN") (pin "23") (pinfunction "XERR_23") (pintype "open_collector"))
      (node (ref "PIC32MX330F064H") (pin "64") (pinfunction "AN21/PMD4/RE4_64") (pintype "bidirectional"))
      (node (ref "R7") (pin "1") (pinfunction "1_1") (pintype "passive"))
      (node (ref "ROOD") (pin "23") (pinfunction "XERR_23") (pintype "open_collector"))
    )
    (net (code "165") (name "TLC_XLAT") (class "Default")
      (node (ref "BLAUW") (pin "3") (pinfunction "XLAT_3") (pintype "input"))
      (node (ref "GROEN") (pin "3") (pinfunction "XLAT_3") (pintype "input"))
      (node (ref "PIC32MX330F064H") (pin "2") (pinfunction "AN23/PMD6/RE6_2") (pintype "bidirectional"))
      (node (ref "R60") (pin "2") (pinfunction "2_2") (pintype "passive"))
      (node (ref "ROOD") (pin "3") (pinfunction "XLAT_3") (pintype "input"))
    )
    (net (code "166") (name "unconnected-(BTB_CONN-Pad2)") (class "Default")
      (node (ref "BTB_CONN") (pin "2") (pinfunction "2_2") (pintype "passive"))
    )
    (net (code "167") (name "unconnected-(BTB_CONN-Pad8)") (class "Default")
      (node (ref "BTB_CONN") (pin "8") (pinfunction "8_8") (pintype "passive"))
    )
    (net (code "168") (name "unconnected-(BTB_CONN-Pad12)") (class "Default")
      (node (ref "BTB_CONN") (pin "12") (pinfunction "12_12") (pintype "passive"))
    )
    (net (code "169") (name "unconnected-(BTB_CONN-Pad13)") (class "Default")
      (node (ref "BTB_CONN") (pin "13") (pinfunction "13_13") (pintype "passive"))
    )
    (net (code "170") (name "unconnected-(BTB_CONN-Pad14)") (class "Default")
      (node (ref "BTB_CONN") (pin "14") (pinfunction "14_14") (pintype "passive"))
    )
    (net (code "171") (name "unconnected-(BTB_CONN-Pad15)") (class "Default")
      (node (ref "BTB_CONN") (pin "15") (pinfunction "15_15") (pintype "passive"))
    )
    (net (code "172") (name "unconnected-(BTB_CONN-Pad16)") (class "Default")
      (node (ref "BTB_CONN") (pin "16") (pinfunction "16_16") (pintype "passive"))
    )
    (net (code "173") (name "unconnected-(PIC32MX330F064H-AN4{slash}C1INB{slash}RB4-Pad12)") (class "Default")
      (node (ref "PIC32MX330F064H") (pin "12") (pinfunction "AN4/C1INB/RB4_12") (pintype "bidirectional"))
    )
    (net (code "174") (name "unconnected-(PIC32MX330F064H-AN8{slash}RPB8{slash}CTED10{slash}{slash}RB8-Pad21)") (class "Default")
      (node (ref "PIC32MX330F064H") (pin "21") (pinfunction "AN8/RPB8/CTED10//RB8_21") (pintype "bidirectional"))
    )
    (net (code "175") (name "unconnected-(PIC32MX330F064H-AN9{slash}RPB9{slash}CTED4{slash}PMA7{slash}RB9-Pad22)") (class "Default")
      (node (ref "PIC32MX330F064H") (pin "22") (pinfunction "AN9/RPB9/CTED4/PMA7/RB9_22") (pintype "bidirectional"))
    )
    (net (code "176") (name "unconnected-(PIC32MX330F064H-AN14{slash}RPB14{slash}CTED5{slash}PMA1{slash}RB14-Pad29)") (class "Default")
      (node (ref "PIC32MX330F064H") (pin "29") (pinfunction "AN14/RPB14/CTED5/PMA1/RB14_29") (pintype "bidirectional"))
    )
    (net (code "177") (name "unconnected-(PIC32MX330F064H-PGEC2{slash}AN6{slash}RPB6{slash}RB6-Pad17)") (class "Default")
      (node (ref "PIC32MX330F064H") (pin "17") (pinfunction "PGEC2/AN6/RPB6/RB6_17") (pintype "bidirectional"))
    )
    (net (code "178") (name "unconnected-(PIC32MX330F064H-RPF0{slash}RF0-Pad58)") (class "Default")
      (node (ref "PIC32MX330F064H") (pin "58") (pinfunction "RPF0/RF0_58") (pintype "bidirectional"))
    )
    (net (code "179") (name "unconnected-(PIC32MX330F064H-RPF1{slash}RF1-Pad59)") (class "Default")
      (node (ref "PIC32MX330F064H") (pin "59") (pinfunction "RPF1/RF1_59") (pintype "bidirectional"))
    )
    (net (code "180") (name "unconnected-(PIC32MX330F064H-SCL1{slash}RG2-Pad37)") (class "Default")
      (node (ref "PIC32MX330F064H") (pin "37") (pinfunction "SCL1/RG2_37") (pintype "bidirectional"))
    )
    (net (code "181") (name "unconnected-(PIC32MX330F064H-SDA1{slash}RG3-Pad36)") (class "Default")
      (node (ref "PIC32MX330F064H") (pin "36") (pinfunction "SDA1/RG3_36") (pintype "bidirectional"))
    )
    (net (code "182") (name "unconnected-(PIC32MX330F064H-SOSCI{slash}RPC13{slash}RC13-Pad47)") (class "Default")
      (node (ref "PIC32MX330F064H") (pin "47") (pinfunction "SOSCI/RPC13/RC13_47") (pintype "bidirectional"))
    )
    (net (code "183") (name "unconnected-(PIC32MX330F064H-SOSCO{slash}RPC14{slash}T1CK{slash}RC14-Pad48)") (class "Default")
      (node (ref "PIC32MX330F064H") (pin "48") (pinfunction "SOSCO/RPC14/T1CK/RC14_48") (pintype "bidirectional"))
    )
    (net (code "184") (name "unconnected-(PIC32MX330F064H-TDO{slash}AN11{slash}PMA12{slash}RB11-Pad24)") (class "Default")
      (node (ref "PIC32MX330F064H") (pin "24") (pinfunction "TDO/AN11/PMA12/RB11_24") (pintype "bidirectional"))
    )
    (net (code "185") (name "unconnected-(PIC32MX330F064H-TMS{slash}CVREFOUT{slash}AN10{slash}RPB10{slash}CTED11{slash}{slash}PMA13{slash}RB10-Pad23)") (class "Default")
      (node (ref "PIC32MX330F064H") (pin "23") (pinfunction "TMS/CVREFOUT/AN10/RPB10/CTED11//PMA13/RB10_23") (pintype "bidirectional"))
    )
    (net (code "186") (name "unconnected-(ULN1-Pad10)") (class "Default")
      (node (ref "ULN1") (pin "10") (pinfunction "10_10") (pintype "bidirectional"))
    )
    (net (code "187") (name "unconnected-(ULN2-Pad10)") (class "Default")
      (node (ref "ULN2") (pin "10") (pinfunction "10_10") (pintype "bidirectional"))
    )
  )
)
